# marbles_v70.net
KiCad netlist of a schematic drawn in EAGLE
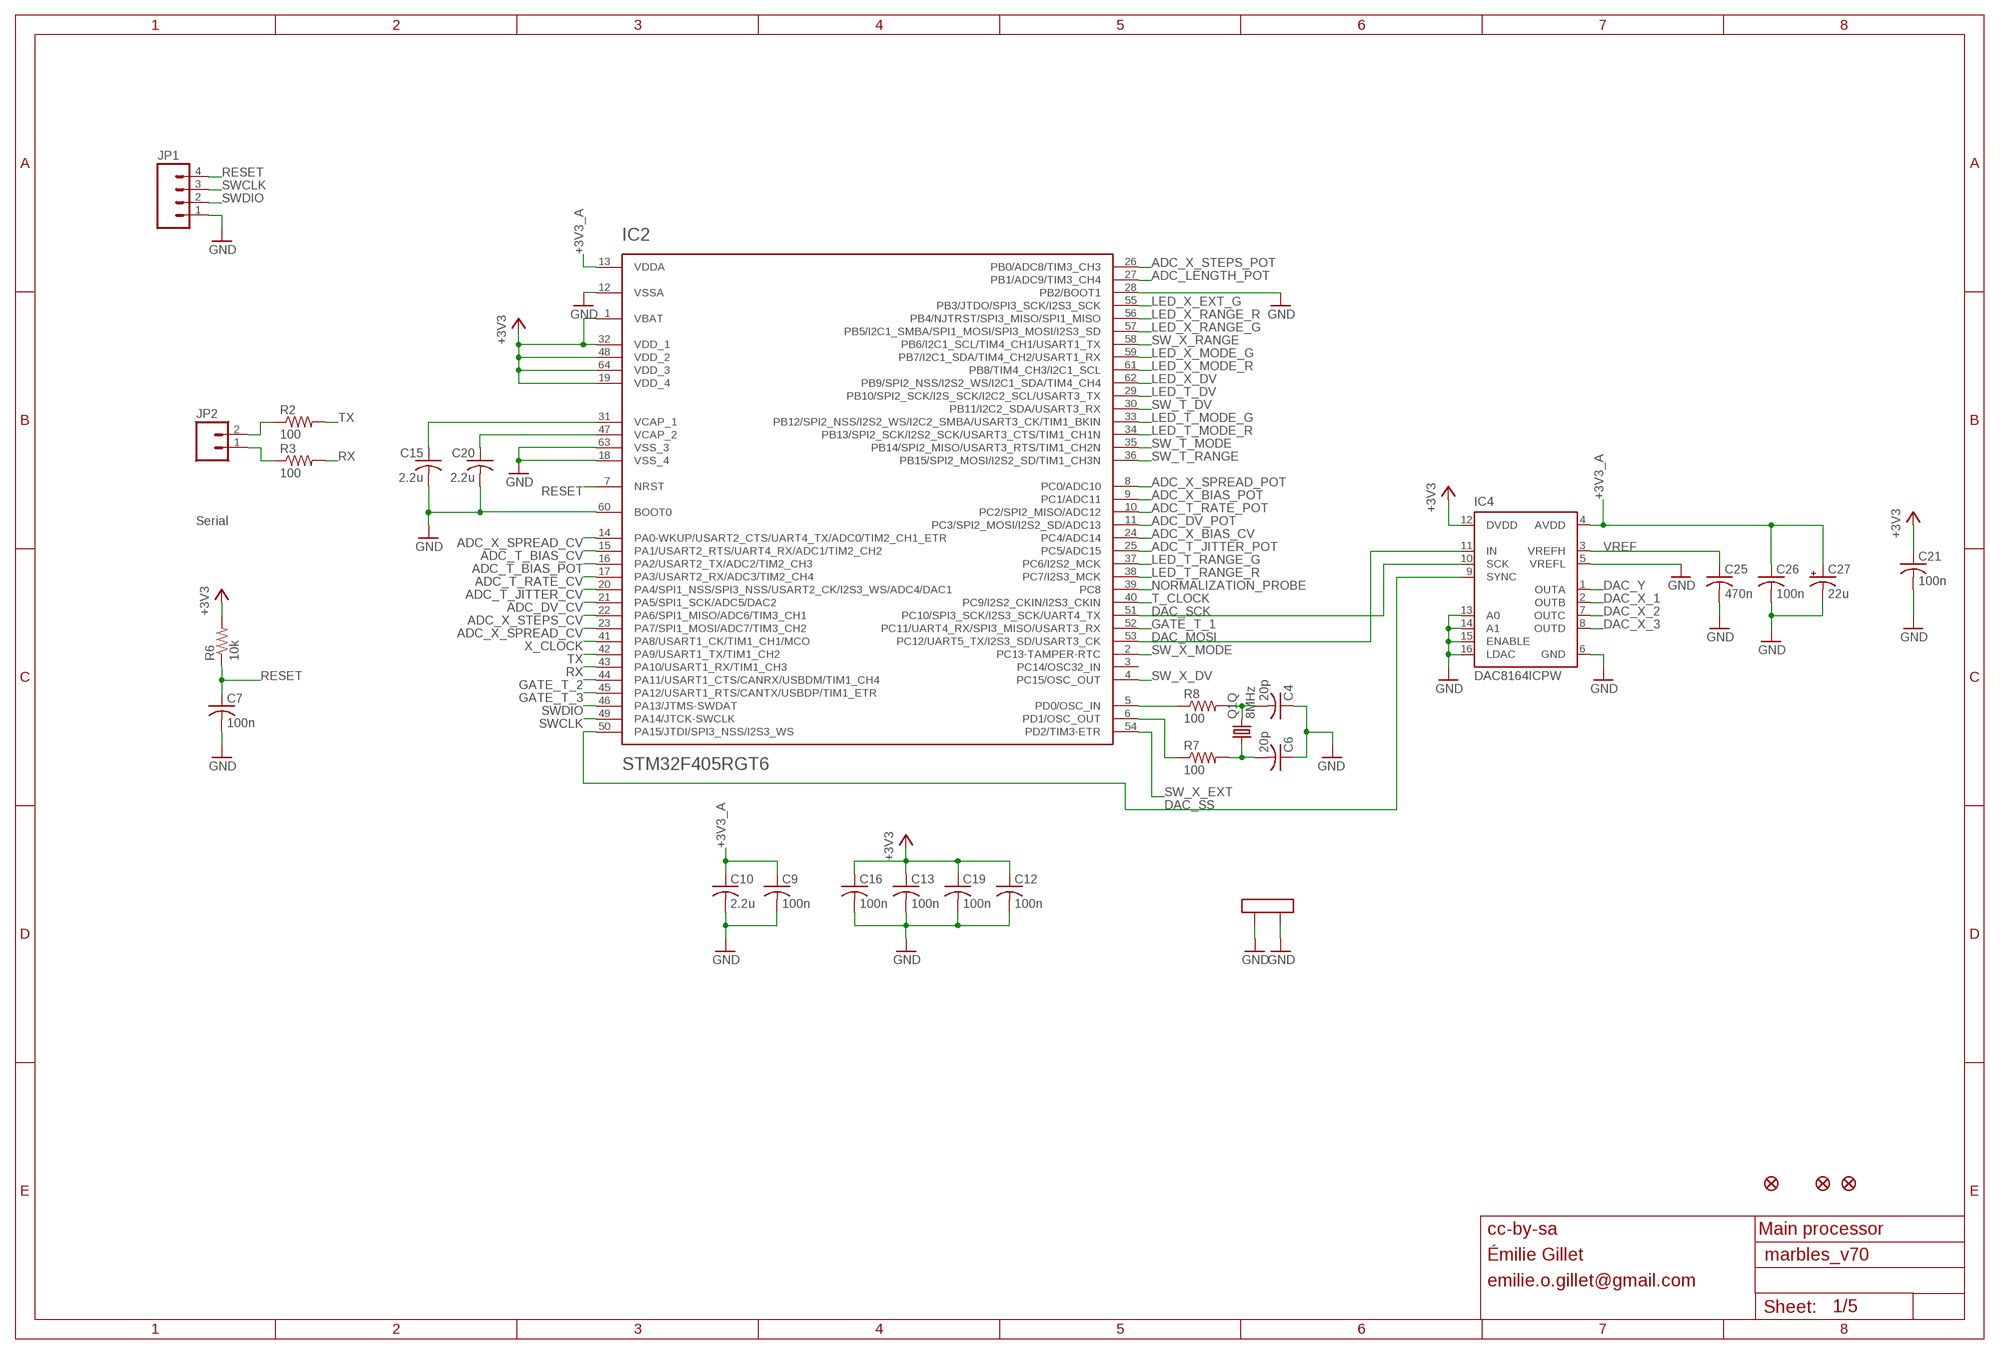
[diagram p0: schematic, sheet 1]
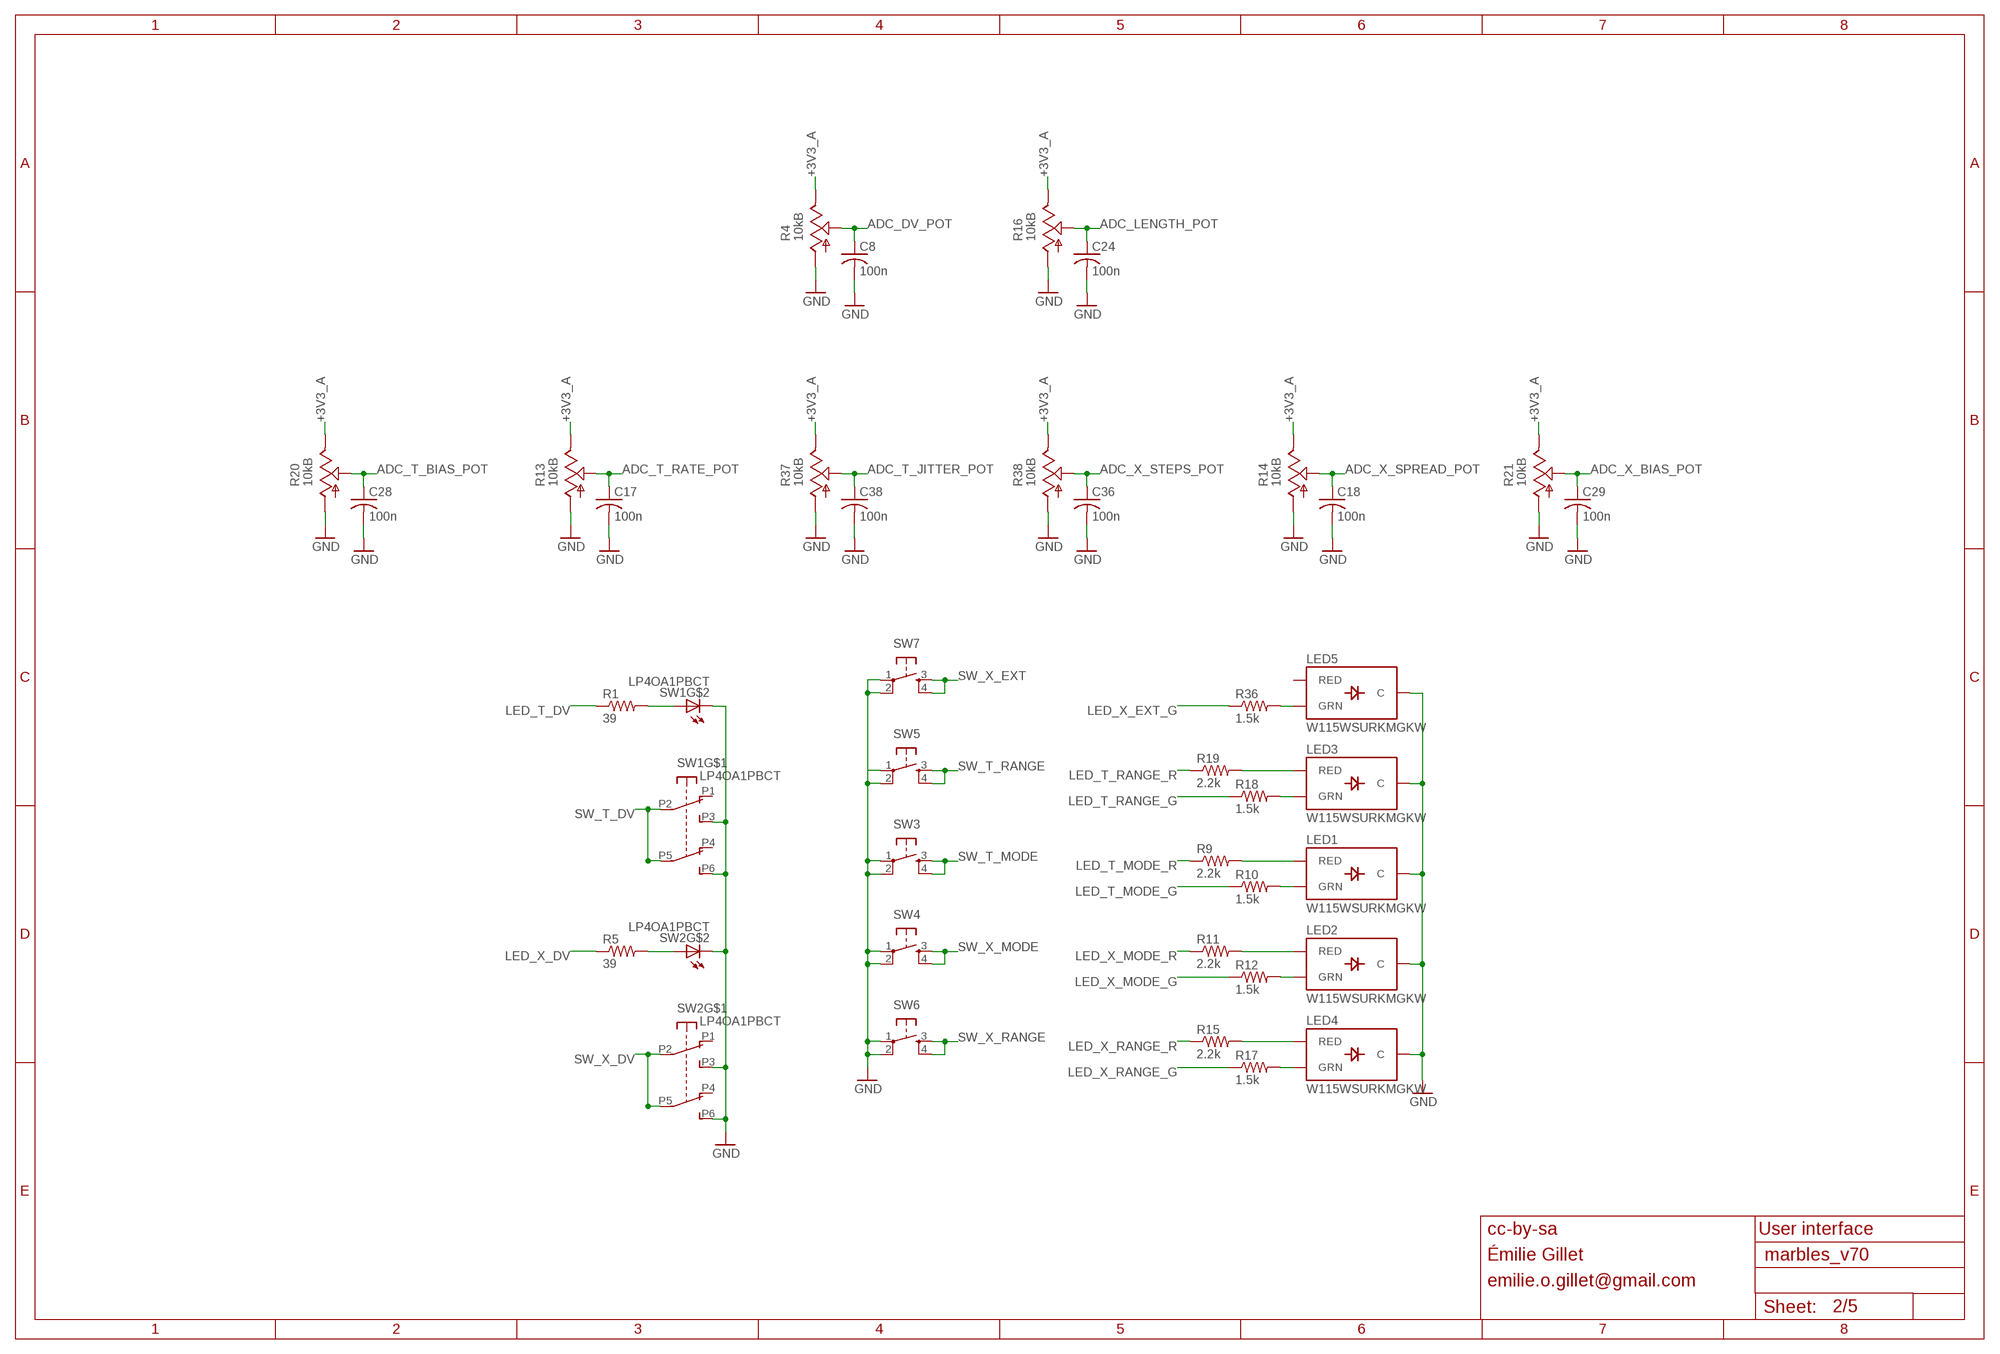
[diagram p1: schematic, sheet 2]
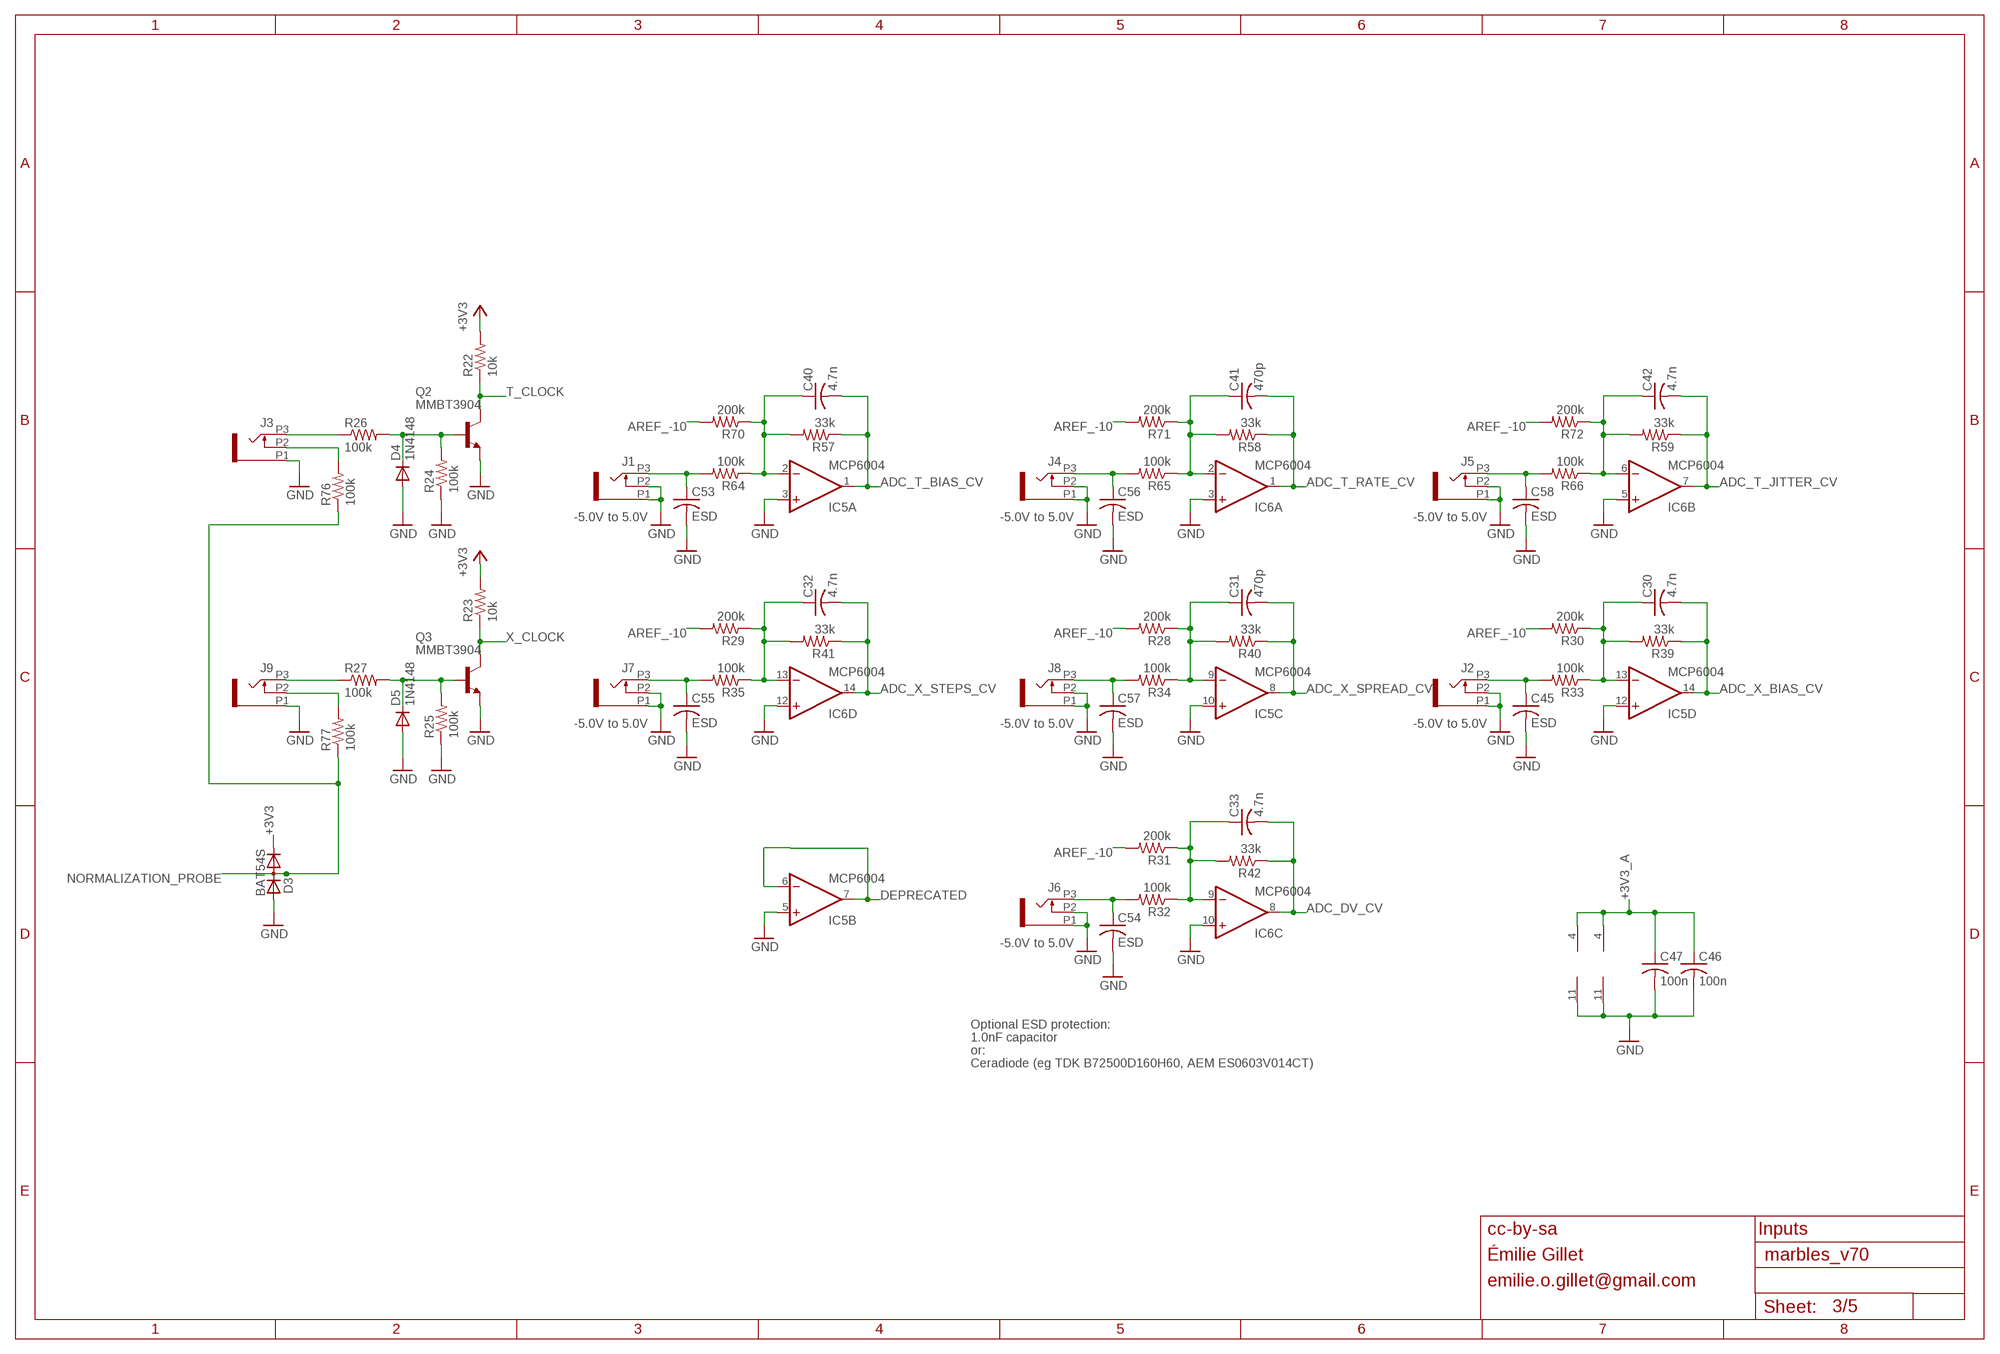
[diagram p2: schematic, sheet 3]
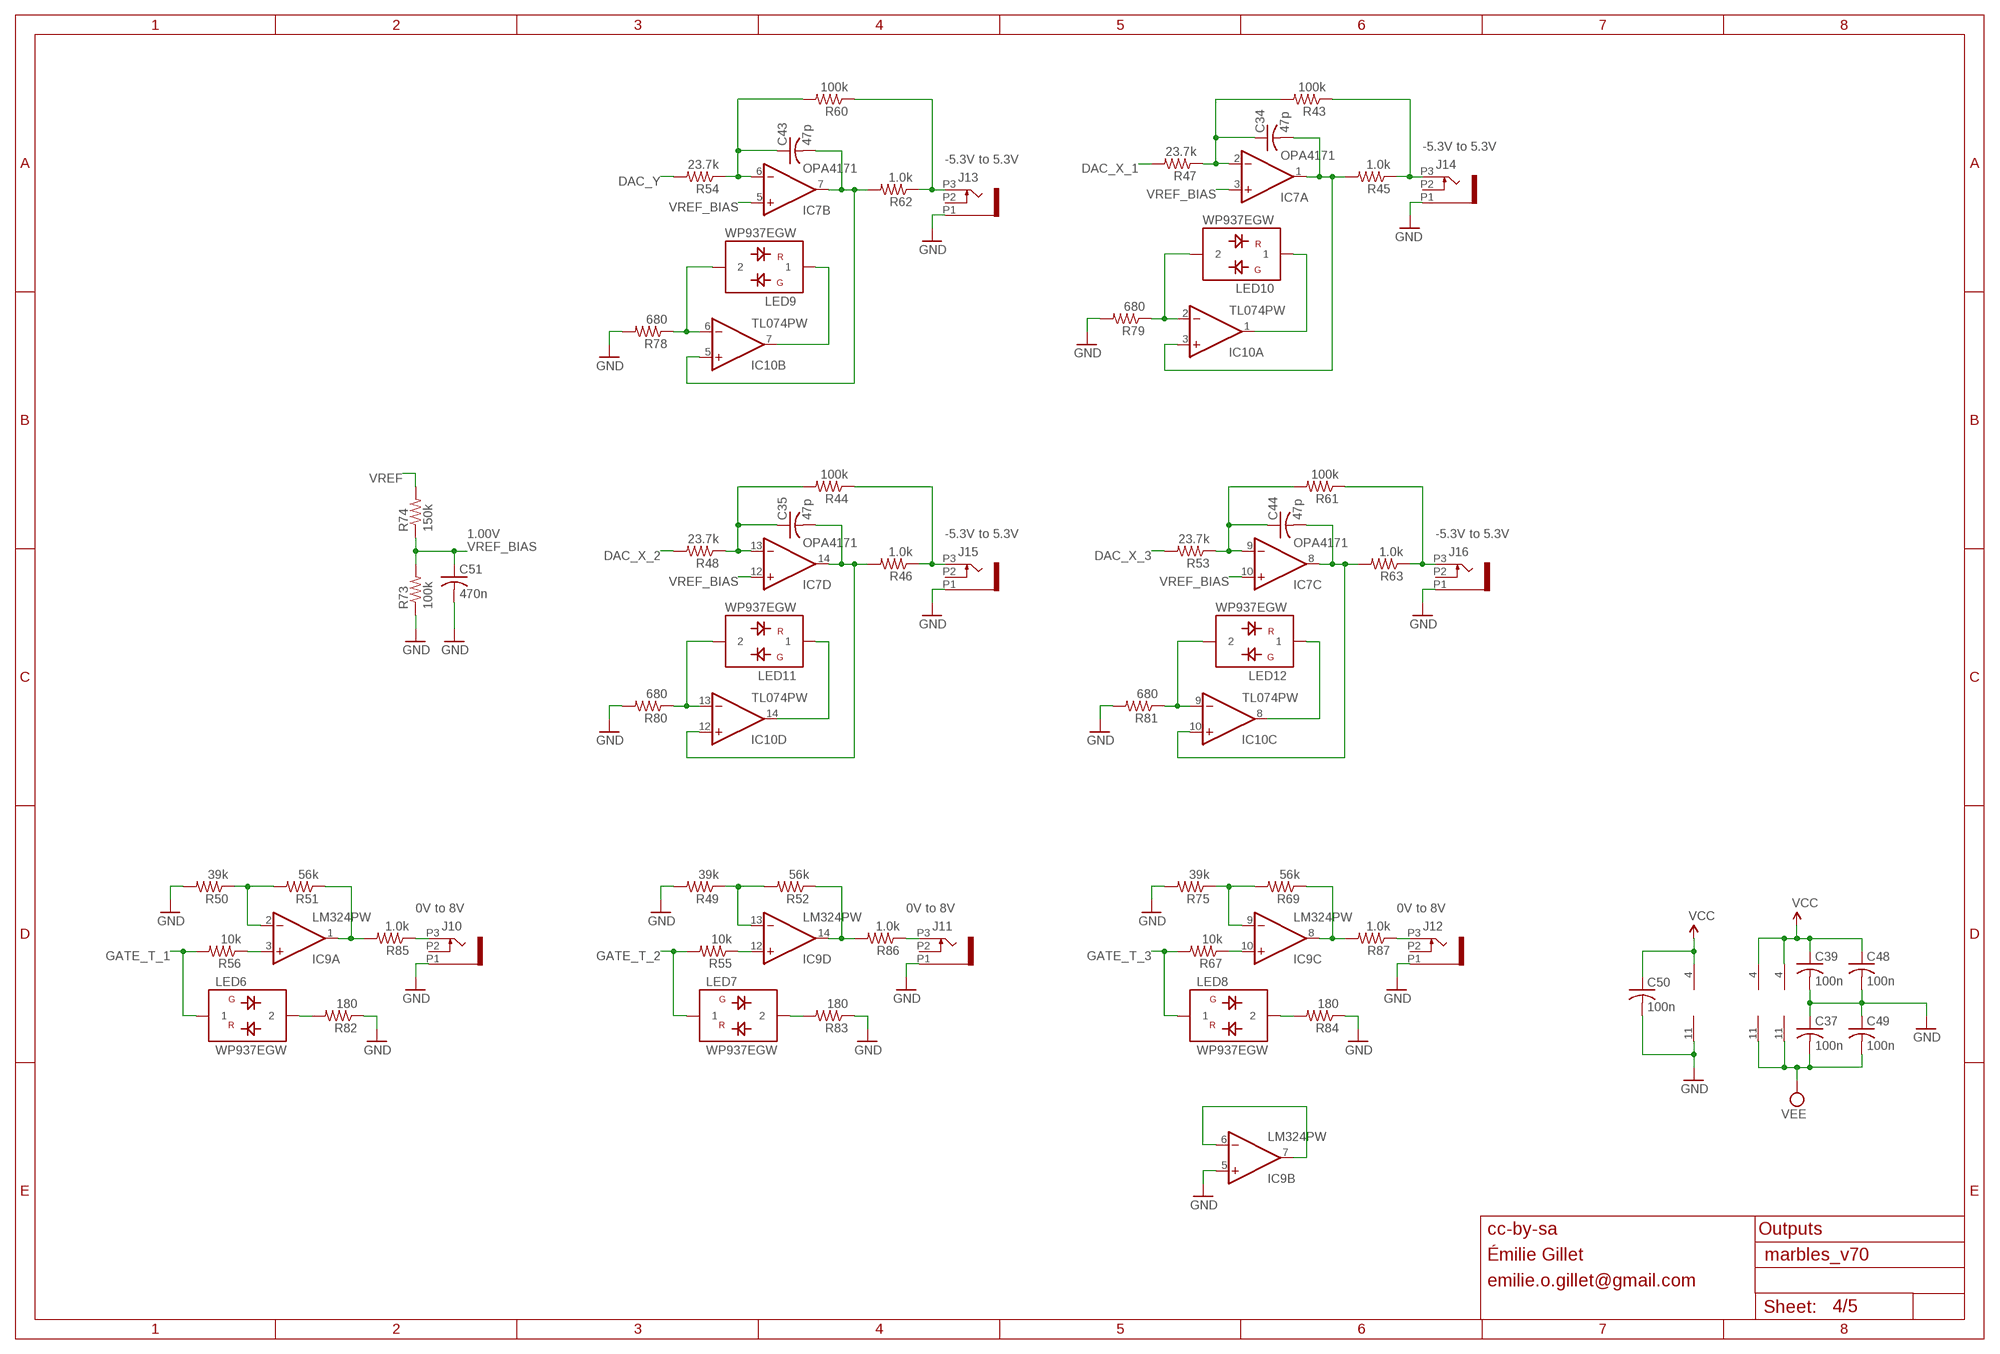
[diagram p3: schematic, sheet 4]
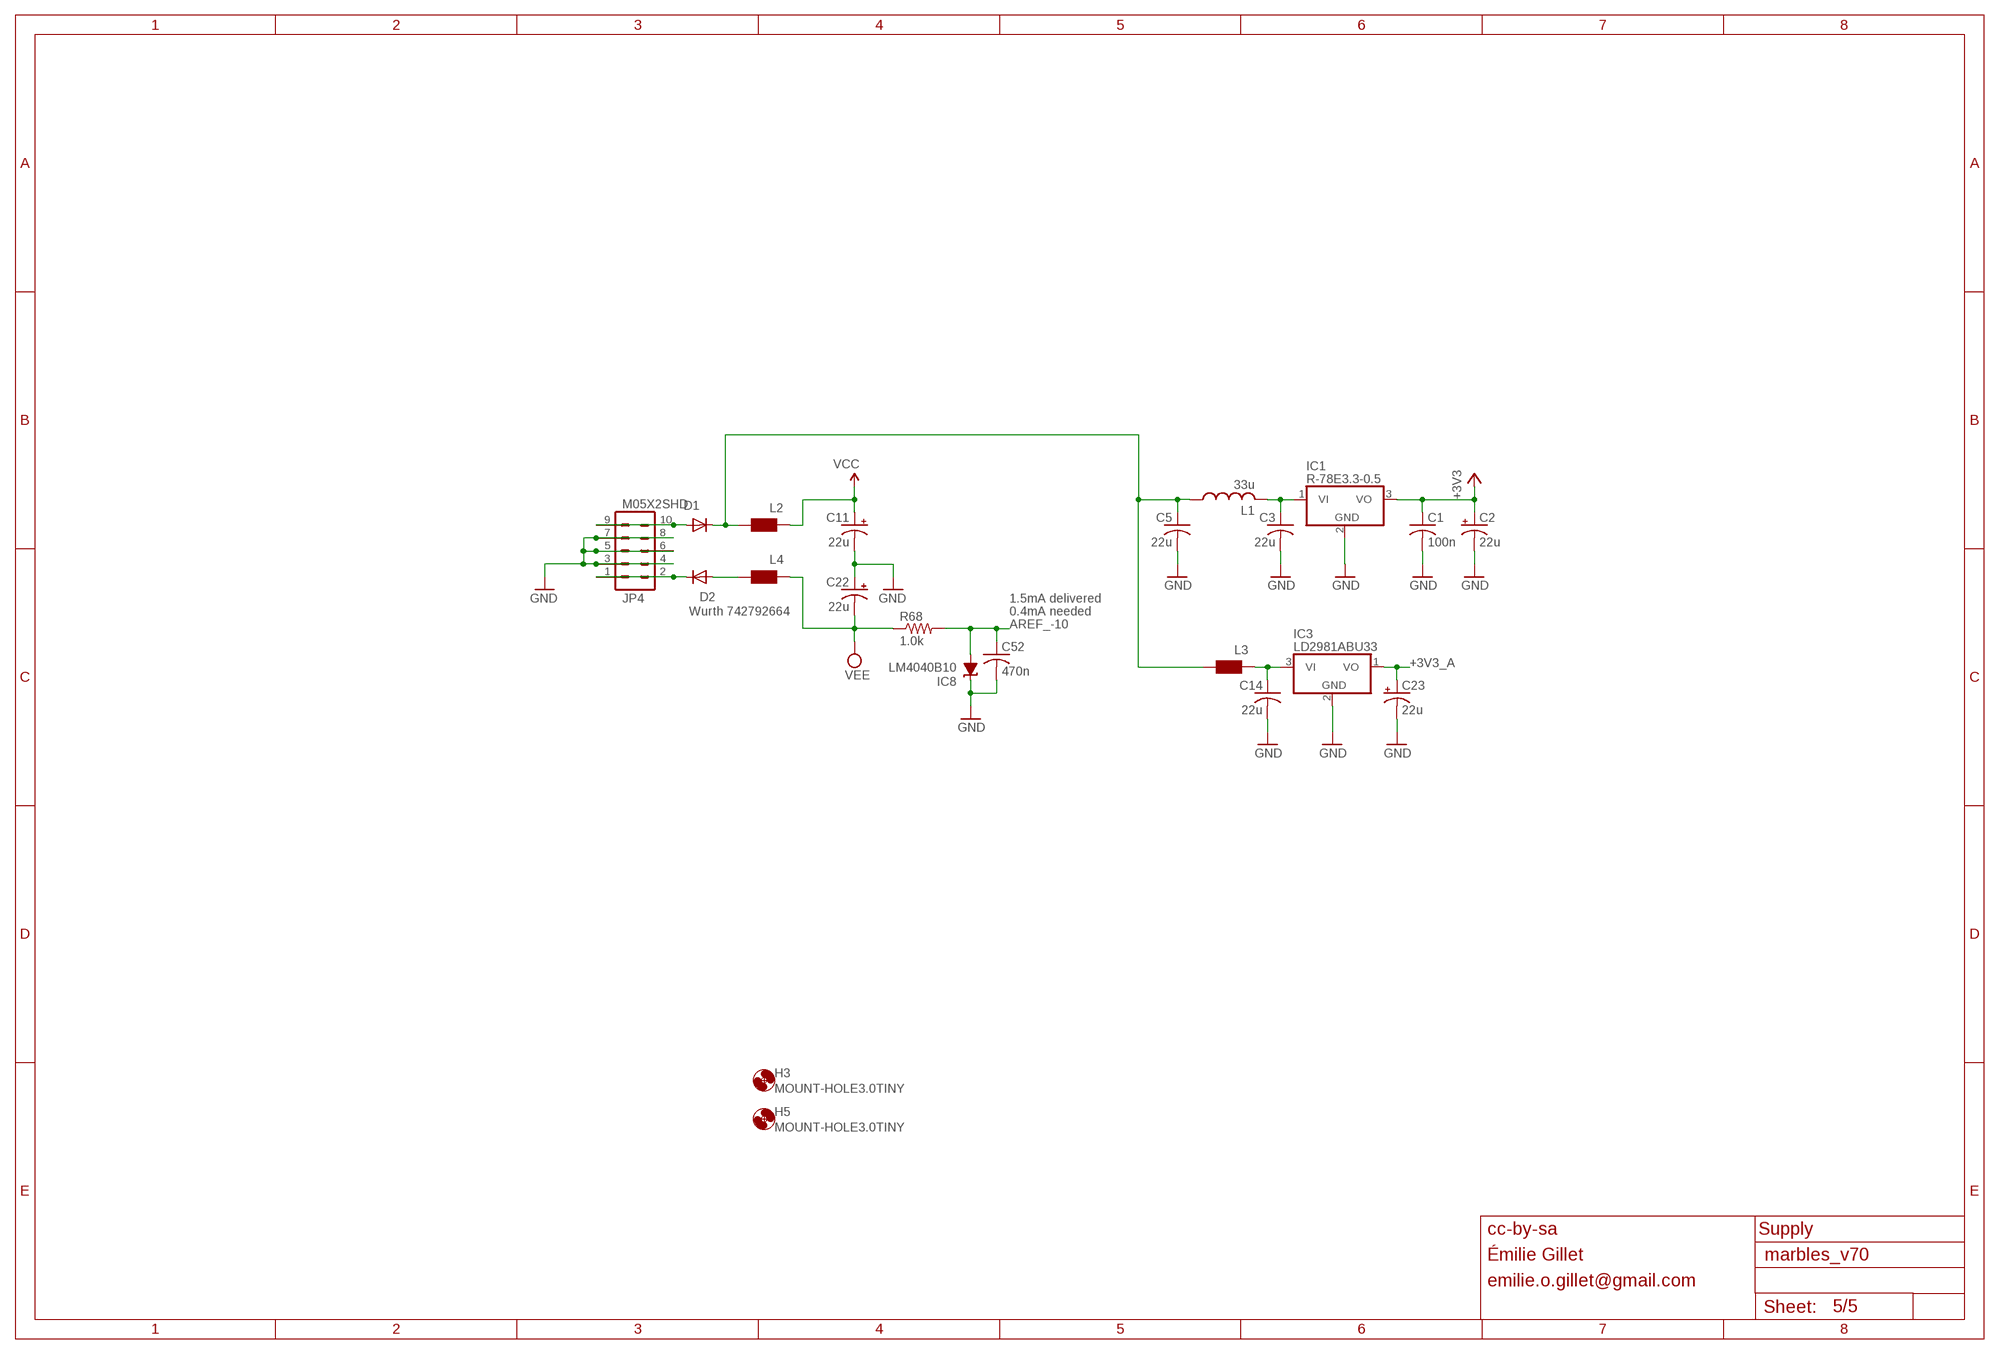
[diagram p4: schematic, sheet 5]

(export (version "E")
  (design (tool "Eeschema 10.0.6"))
  (components
    (comp (ref "C8")
      (value "100n")
      (footprint "eagle-import:C0402")
      (libsource (lib "eagle-import") (part "C-USC0402"))
    )
    (comp (ref "C17")
      (value "100n")
      (footprint "eagle-import:C0402")
      (libsource (lib "eagle-import") (part "C-USC0402"))
    )
    (comp (ref "C18")
      (value "100n")
      (footprint "eagle-import:C0402")
      (libsource (lib "eagle-import") (part "C-USC0402"))
    )
    (comp (ref "C24")
      (value "100n")
      (footprint "eagle-import:C0402")
      (libsource (lib "eagle-import") (part "C-USC0402"))
    )
    (comp (ref "C28")
      (value "100n")
      (footprint "eagle-import:C0402")
      (libsource (lib "eagle-import") (part "C-USC0402"))
    )
    (comp (ref "C29")
      (value "100n")
      (footprint "eagle-import:C0402")
      (libsource (lib "eagle-import") (part "C-USC0402"))
    )
    (comp (ref "C36")
      (value "100n")
      (footprint "eagle-import:C0402")
      (libsource (lib "eagle-import") (part "C-USC0402"))
    )
    (comp (ref "C38")
      (value "100n")
      (footprint "eagle-import:C0402")
      (libsource (lib "eagle-import") (part "C-USC0402"))
    )
    (comp (ref "LED1")
      (value "W115WSURKMGKW")
      (footprint "eagle-import:LED-BICOLOR-THROUGHHOLE-2.54")
      (libsource (lib "eagle-import") (part "LED-BICOLOR-THROUGHHOLE2.54"))
    )
    (comp (ref "LED2")
      (value "W115WSURKMGKW")
      (footprint "eagle-import:LED-BICOLOR-THROUGHHOLE-2.54")
      (libsource (lib "eagle-import") (part "LED-BICOLOR-THROUGHHOLE2.54"))
    )
    (comp (ref "LED3")
      (value "W115WSURKMGKW")
      (footprint "eagle-import:LED-BICOLOR-THROUGHHOLE-2.54")
      (libsource (lib "eagle-import") (part "LED-BICOLOR-THROUGHHOLE2.54"))
    )
    (comp (ref "LED4")
      (value "W115WSURKMGKW")
      (footprint "eagle-import:LED-BICOLOR-THROUGHHOLE-2.54")
      (libsource (lib "eagle-import") (part "LED-BICOLOR-THROUGHHOLE2.54"))
    )
    (comp (ref "LED5")
      (value "W115WSURKMGKW")
      (footprint "eagle-import:LED-BICOLOR-THROUGHHOLE-2.54")
      (libsource (lib "eagle-import") (part "LED-BICOLOR-THROUGHHOLE2.54"))
    )
    (comp (ref "R1")
      (value "39")
      (footprint "eagle-import:R0402")
      (libsource (lib "eagle-import") (part "R-US_R0402"))
    )
    (comp (ref "R4")
      (value "10kB")
      (footprint "eagle-import:ALPS_POT_VERTICAL_PS")
      (libsource (lib "eagle-import") (part "POT_USVERTICAL_PS"))
    )
    (comp (ref "R5")
      (value "39")
      (footprint "eagle-import:R0402")
      (libsource (lib "eagle-import") (part "R-US_R0402"))
    )
    (comp (ref "R9")
      (value "2.2k")
      (footprint "eagle-import:R0402")
      (libsource (lib "eagle-import") (part "R-US_R0402"))
    )
    (comp (ref "R10")
      (value "1.5k")
      (footprint "eagle-import:R0402")
      (libsource (lib "eagle-import") (part "R-US_R0402"))
    )
    (comp (ref "R11")
      (value "2.2k")
      (footprint "eagle-import:R0402")
      (libsource (lib "eagle-import") (part "R-US_R0402"))
    )
    (comp (ref "R12")
      (value "1.5k")
      (footprint "eagle-import:R0402")
      (libsource (lib "eagle-import") (part "R-US_R0402"))
    )
    (comp (ref "R13")
      (value "10kB")
      (footprint "eagle-import:ALPS_POT_VERTICAL_PS")
      (libsource (lib "eagle-import") (part "POT_USVERTICAL_PS"))
    )
    (comp (ref "R14")
      (value "10kB")
      (footprint "eagle-import:ALPS_POT_VERTICAL_PS")
      (libsource (lib "eagle-import") (part "POT_USVERTICAL_PS"))
    )
    (comp (ref "R15")
      (value "2.2k")
      (footprint "eagle-import:R0402")
      (libsource (lib "eagle-import") (part "R-US_R0402"))
    )
    (comp (ref "R16")
      (value "10kB")
      (footprint "eagle-import:ALPS_POT_VERTICAL_PS")
      (libsource (lib "eagle-import") (part "POT_USVERTICAL_PS"))
    )
    (comp (ref "R17")
      (value "1.5k")
      (footprint "eagle-import:R0402")
      (libsource (lib "eagle-import") (part "R-US_R0402"))
    )
    (comp (ref "R18")
      (value "1.5k")
      (footprint "eagle-import:R0402")
      (libsource (lib "eagle-import") (part "R-US_R0402"))
    )
    (comp (ref "R19")
      (value "2.2k")
      (footprint "eagle-import:R0402")
      (libsource (lib "eagle-import") (part "R-US_R0402"))
    )
    (comp (ref "R20")
      (value "10kB")
      (footprint "eagle-import:ALPS_POT_VERTICAL_PS")
      (libsource (lib "eagle-import") (part "POT_USVERTICAL_PS"))
    )
    (comp (ref "R21")
      (value "10kB")
      (footprint "eagle-import:ALPS_POT_VERTICAL_PS")
      (libsource (lib "eagle-import") (part "POT_USVERTICAL_PS"))
    )
    (comp (ref "R36")
      (value "1.5k")
      (footprint "eagle-import:R0402")
      (libsource (lib "eagle-import") (part "R-US_R0402"))
    )
    (comp (ref "R37")
      (value "10kB")
      (footprint "eagle-import:ALPS_POT_VERTICAL_PS")
      (libsource (lib "eagle-import") (part "POT_USVERTICAL_PS"))
    )
    (comp (ref "R38")
      (value "10kB")
      (footprint "eagle-import:ALPS_POT_VERTICAL_PS")
      (libsource (lib "eagle-import") (part "POT_USVERTICAL_PS"))
    )
    (comp (ref "SW1")
      (value "LP4OA1PBCT")
      (footprint "eagle-import:LP4OA1PBCT")
      (libsource (lib "eagle-import") (part "LP4OA1PBCT"))
    )
    (comp (ref "SW2")
      (value "LP4OA1PBCT")
      (footprint "eagle-import:LP4OA1PBCT")
      (libsource (lib "eagle-import") (part "LP4OA1PBCT"))
    )
    (comp (ref "SW3")
      (value "TAC_SWITCHPTH")
      (footprint "eagle-import:TACTILE-PTH")
      (libsource (lib "eagle-import") (part "TAC_SWITCHPTH"))
    )
    (comp (ref "SW4")
      (value "TAC_SWITCHPTH")
      (footprint "eagle-import:TACTILE-PTH")
      (libsource (lib "eagle-import") (part "TAC_SWITCHPTH"))
    )
    (comp (ref "SW5")
      (value "TAC_SWITCHPTH")
      (footprint "eagle-import:TACTILE-PTH")
      (libsource (lib "eagle-import") (part "TAC_SWITCHPTH"))
    )
    (comp (ref "SW6")
      (value "TAC_SWITCHPTH")
      (footprint "eagle-import:TACTILE-PTH")
      (libsource (lib "eagle-import") (part "TAC_SWITCHPTH"))
    )
    (comp (ref "SW7")
      (value "TAC_SWITCHPTH")
      (footprint "eagle-import:TACTILE-PTH")
      (libsource (lib "eagle-import") (part "TAC_SWITCHPTH"))
    )
    (comp (ref "C34")
      (value "47p")
      (footprint "eagle-import:C0402")
      (libsource (lib "eagle-import") (part "C-USC0402"))
    )
    (comp (ref "C35")
      (value "47p")
      (footprint "eagle-import:C0402")
      (libsource (lib "eagle-import") (part "C-USC0402"))
    )
    (comp (ref "C37")
      (value "100n")
      (footprint "eagle-import:C0402")
      (libsource (lib "eagle-import") (part "C-USC0402"))
    )
    (comp (ref "C39")
      (value "100n")
      (footprint "eagle-import:C0402")
      (libsource (lib "eagle-import") (part "C-USC0402"))
    )
    (comp (ref "C43")
      (value "47p")
      (footprint "eagle-import:C0402")
      (libsource (lib "eagle-import") (part "C-USC0402"))
    )
    (comp (ref "C44")
      (value "47p")
      (footprint "eagle-import:C0402")
      (libsource (lib "eagle-import") (part "C-USC0402"))
    )
    (comp (ref "C48")
      (value "100n")
      (footprint "eagle-import:C0402")
      (libsource (lib "eagle-import") (part "C-USC0402"))
    )
    (comp (ref "C49")
      (value "100n")
      (footprint "eagle-import:C0402")
      (libsource (lib "eagle-import") (part "C-USC0402"))
    )
    (comp (ref "C50")
      (value "100n")
      (footprint "eagle-import:C0402")
      (libsource (lib "eagle-import") (part "C-USC0402"))
    )
    (comp (ref "C51")
      (value "470n")
      (footprint "eagle-import:C0402")
      (libsource (lib "eagle-import") (part "C-USC0402"))
    )
    (comp (ref "IC7")
      (value "OPA4171")
      (footprint "eagle-import:TSSOP14_065")
      (libsource (lib "eagle-import") (part "TL074PW"))
    )
    (comp (ref "IC9")
      (value "LM324PW")
      (footprint "eagle-import:TSSOP14_065")
      (libsource (lib "eagle-import") (part "TL074PW"))
    )
    (comp (ref "IC10")
      (value "TL074PW")
      (footprint "eagle-import:TSSOP14_065")
      (libsource (lib "eagle-import") (part "TL074PW"))
    )
    (comp (ref "J10")
      (value "PJ301_THONKICONN6")
      (footprint "eagle-import:WQP_PJ_301M6")
      (libsource (lib "eagle-import") (part "PJ301_THONKICONN6"))
    )
    (comp (ref "J11")
      (value "PJ301_THONKICONN6")
      (footprint "eagle-import:WQP_PJ_301M6")
      (libsource (lib "eagle-import") (part "PJ301_THONKICONN6"))
    )
    (comp (ref "J12")
      (value "PJ301_THONKICONN6")
      (footprint "eagle-import:WQP_PJ_301M6")
      (libsource (lib "eagle-import") (part "PJ301_THONKICONN6"))
    )
    (comp (ref "J13")
      (value "PJ301_THONKICONN6")
      (footprint "eagle-import:WQP_PJ_301M6")
      (libsource (lib "eagle-import") (part "PJ301_THONKICONN6"))
    )
    (comp (ref "J14")
      (value "PJ301_THONKICONN6")
      (footprint "eagle-import:WQP_PJ_301M6")
      (libsource (lib "eagle-import") (part "PJ301_THONKICONN6"))
    )
    (comp (ref "J15")
      (value "PJ301_THONKICONN6")
      (footprint "eagle-import:WQP_PJ_301M6")
      (libsource (lib "eagle-import") (part "PJ301_THONKICONN6"))
    )
    (comp (ref "J16")
      (value "PJ301_THONKICONN6")
      (footprint "eagle-import:WQP_PJ_301M6")
      (libsource (lib "eagle-import") (part "PJ301_THONKICONN6"))
    )
    (comp (ref "LED6")
      (value "WP937EGW")
      (footprint "eagle-import:LED3MM")
      (libsource (lib "eagle-import") (part "LED-BICOLOR-SHARED-THROUGHHOLE"))
    )
    (comp (ref "LED7")
      (value "WP937EGW")
      (footprint "eagle-import:LED3MM")
      (libsource (lib "eagle-import") (part "LED-BICOLOR-SHARED-THROUGHHOLE"))
    )
    (comp (ref "LED8")
      (value "WP937EGW")
      (footprint "eagle-import:LED3MM")
      (libsource (lib "eagle-import") (part "LED-BICOLOR-SHARED-THROUGHHOLE"))
    )
    (comp (ref "LED9")
      (value "WP937EGW")
      (footprint "eagle-import:LED3MM")
      (libsource (lib "eagle-import") (part "LED-BICOLOR-SHARED-THROUGHHOLE"))
    )
    (comp (ref "LED10")
      (value "WP937EGW")
      (footprint "eagle-import:LED3MM")
      (libsource (lib "eagle-import") (part "LED-BICOLOR-SHARED-THROUGHHOLE"))
    )
    (comp (ref "LED11")
      (value "WP937EGW")
      (footprint "eagle-import:LED3MM")
      (libsource (lib "eagle-import") (part "LED-BICOLOR-SHARED-THROUGHHOLE"))
    )
    (comp (ref "LED12")
      (value "WP937EGW")
      (footprint "eagle-import:LED3MM")
      (libsource (lib "eagle-import") (part "LED-BICOLOR-SHARED-THROUGHHOLE"))
    )
    (comp (ref "R43")
      (value "100k")
      (footprint "eagle-import:R0402")
      (libsource (lib "eagle-import") (part "R-US_R0402"))
    )
    (comp (ref "R44")
      (value "100k")
      (footprint "eagle-import:R0402")
      (libsource (lib "eagle-import") (part "R-US_R0402"))
    )
    (comp (ref "R45")
      (value "1.0k")
      (footprint "eagle-import:R0603")
      (libsource (lib "eagle-import") (part "R-US_R0603"))
    )
    (comp (ref "R46")
      (value "1.0k")
      (footprint "eagle-import:R0603")
      (libsource (lib "eagle-import") (part "R-US_R0603"))
    )
    (comp (ref "R47")
      (value "23.7k")
      (footprint "eagle-import:R0402")
      (libsource (lib "eagle-import") (part "R-US_R0402"))
    )
    (comp (ref "R48")
      (value "23.7k")
      (footprint "eagle-import:R0402")
      (libsource (lib "eagle-import") (part "R-US_R0402"))
    )
    (comp (ref "R49")
      (value "39k")
      (footprint "eagle-import:R0402")
      (libsource (lib "eagle-import") (part "R-US_R0402"))
    )
    (comp (ref "R50")
      (value "39k")
      (footprint "eagle-import:R0402")
      (libsource (lib "eagle-import") (part "R-US_R0402"))
    )
    (comp (ref "R51")
      (value "56k")
      (footprint "eagle-import:R0402")
      (libsource (lib "eagle-import") (part "R-US_R0402"))
    )
    (comp (ref "R52")
      (value "56k")
      (footprint "eagle-import:R0402")
      (libsource (lib "eagle-import") (part "R-US_R0402"))
    )
    (comp (ref "R53")
      (value "23.7k")
      (footprint "eagle-import:R0402")
      (libsource (lib "eagle-import") (part "R-US_R0402"))
    )
    (comp (ref "R54")
      (value "23.7k")
      (footprint "eagle-import:R0402")
      (libsource (lib "eagle-import") (part "R-US_R0402"))
    )
    (comp (ref "R55")
      (value "10k")
      (footprint "eagle-import:R0402")
      (libsource (lib "eagle-import") (part "R-US_R0402"))
    )
    (comp (ref "R56")
      (value "10k")
      (footprint "eagle-import:R0402")
      (libsource (lib "eagle-import") (part "R-US_R0402"))
    )
    (comp (ref "R60")
      (value "100k")
      (footprint "eagle-import:R0402")
      (libsource (lib "eagle-import") (part "R-US_R0402"))
    )
    (comp (ref "R61")
      (value "100k")
      (footprint "eagle-import:R0402")
      (libsource (lib "eagle-import") (part "R-US_R0402"))
    )
    (comp (ref "R62")
      (value "1.0k")
      (footprint "eagle-import:R0603")
      (libsource (lib "eagle-import") (part "R-US_R0603"))
    )
    (comp (ref "R63")
      (value "1.0k")
      (footprint "eagle-import:R0603")
      (libsource (lib "eagle-import") (part "R-US_R0603"))
    )
    (comp (ref "R67")
      (value "10k")
      (footprint "eagle-import:R0402")
      (libsource (lib "eagle-import") (part "R-US_R0402"))
    )
    (comp (ref "R69")
      (value "56k")
      (footprint "eagle-import:R0402")
      (libsource (lib "eagle-import") (part "R-US_R0402"))
    )
    (comp (ref "R73")
      (value "100k")
      (footprint "eagle-import:R0402")
      (libsource (lib "eagle-import") (part "R-US_R0402"))
    )
    (comp (ref "R74")
      (value "150k")
      (footprint "eagle-import:R0402")
      (libsource (lib "eagle-import") (part "R-US_R0402"))
    )
    (comp (ref "R75")
      (value "39k")
      (footprint "eagle-import:R0402")
      (libsource (lib "eagle-import") (part "R-US_R0402"))
    )
    (comp (ref "R78")
      (value "680")
      (footprint "eagle-import:R0402")
      (libsource (lib "eagle-import") (part "R-US_R0402"))
    )
    (comp (ref "R79")
      (value "680")
      (footprint "eagle-import:R0402")
      (libsource (lib "eagle-import") (part "R-US_R0402"))
    )
    (comp (ref "R80")
      (value "680")
      (footprint "eagle-import:R0402")
      (libsource (lib "eagle-import") (part "R-US_R0402"))
    )
    (comp (ref "R81")
      (value "680")
      (footprint "eagle-import:R0402")
      (libsource (lib "eagle-import") (part "R-US_R0402"))
    )
    (comp (ref "R82")
      (value "180")
      (footprint "eagle-import:R0402")
      (libsource (lib "eagle-import") (part "R-US_R0402"))
    )
    (comp (ref "R83")
      (value "180")
      (footprint "eagle-import:R0402")
      (libsource (lib "eagle-import") (part "R-US_R0402"))
    )
    (comp (ref "R84")
      (value "180")
      (footprint "eagle-import:R0402")
      (libsource (lib "eagle-import") (part "R-US_R0402"))
    )
    (comp (ref "R85")
      (value "1.0k")
      (footprint "eagle-import:R0603")
      (libsource (lib "eagle-import") (part "R-US_R0603"))
    )
    (comp (ref "R86")
      (value "1.0k")
      (footprint "eagle-import:R0603")
      (libsource (lib "eagle-import") (part "R-US_R0603"))
    )
    (comp (ref "R87")
      (value "1.0k")
      (footprint "eagle-import:R0603")
      (libsource (lib "eagle-import") (part "R-US_R0603"))
    )
    (comp (ref "C4")
      (value "20p")
      (footprint "eagle-import:C0402")
      (libsource (lib "eagle-import") (part "C-USC0402"))
    )
    (comp (ref "C6")
      (value "20p")
      (footprint "eagle-import:C0402")
      (libsource (lib "eagle-import") (part "C-USC0402"))
    )
    (comp (ref "C7")
      (value "100n")
      (footprint "eagle-import:C0402")
      (libsource (lib "eagle-import") (part "C-USC0402"))
    )
    (comp (ref "C9")
      (value "100n")
      (footprint "eagle-import:C0402")
      (libsource (lib "eagle-import") (part "C-USC0402"))
    )
    (comp (ref "C10")
      (value "2.2u")
      (footprint "eagle-import:C0805")
      (libsource (lib "eagle-import") (part "C-USC0805"))
    )
    (comp (ref "C12")
      (value "100n")
      (footprint "eagle-import:C0402")
      (libsource (lib "eagle-import") (part "C-USC0402"))
    )
    (comp (ref "C13")
      (value "100n")
      (footprint "eagle-import:C0402")
      (libsource (lib "eagle-import") (part "C-USC0402"))
    )
    (comp (ref "C15")
      (value "2.2u")
      (footprint "eagle-import:C0805")
      (libsource (lib "eagle-import") (part "C-USC0805"))
    )
    (comp (ref "C16")
      (value "100n")
      (footprint "eagle-import:C0402")
      (libsource (lib "eagle-import") (part "C-USC0402"))
    )
    (comp (ref "C19")
      (value "100n")
      (footprint "eagle-import:C0402")
      (libsource (lib "eagle-import") (part "C-USC0402"))
    )
    (comp (ref "C20")
      (value "2.2u")
      (footprint "eagle-import:C0805")
      (libsource (lib "eagle-import") (part "C-USC0805"))
    )
    (comp (ref "C21")
      (value "100n")
      (footprint "eagle-import:C0402")
      (libsource (lib "eagle-import") (part "C-USC0402"))
    )
    (comp (ref "C25")
      (value "470n")
      (footprint "eagle-import:C0402")
      (libsource (lib "eagle-import") (part "C-USC0402"))
    )
    (comp (ref "C26")
      (value "100n")
      (footprint "eagle-import:C0402")
      (libsource (lib "eagle-import") (part "C-USC0402"))
    )
    (comp (ref "C27")
      (value "22u")
      (footprint "eagle-import:PANASONIC_C")
      (libsource (lib "eagle-import") (part "CPOL-USC"))
    )
    (comp (ref "F1")
      (value "FIDUCIAL1X2")
      (footprint "eagle-import:FIDUCIAL-1X2")
      (libsource (lib "eagle-import") (part "FIDUCIAL1X2"))
    )
    (comp (ref "F2")
      (value "FIDUCIAL1X2")
      (footprint "eagle-import:FIDUCIAL-1X2")
      (libsource (lib "eagle-import") (part "FIDUCIAL1X2"))
    )
    (comp (ref "F3")
      (value "FIDUCIAL1X2")
      (footprint "eagle-import:FIDUCIAL-1X2")
      (libsource (lib "eagle-import") (part "FIDUCIAL1X2"))
    )
    (comp (ref "IC2")
      (value "STM32F405RGT6")
      (footprint "eagle-import:TQFP-10X10-64")
      (libsource (lib "eagle-import") (part "STM32F20X"))
    )
    (comp (ref "IC4")
      (value "DAC8164ICPW")
      (footprint "eagle-import:SOP65P640X110-16N")
      (libsource (lib "eagle-import") (part "DAC8564"))
    )
    (comp (ref "JP1")
      (value "M04PTH")
      (footprint "eagle-import:1X04")
      (libsource (lib "eagle-import") (part "M04PTH"))
    )
    (comp (ref "JP2")
      (value "M02PTH")
      (footprint "eagle-import:1X02")
      (libsource (lib "eagle-import") (part "M02PTH"))
    )
    (comp (ref "Q1")
      (value "8MHz")
      (footprint "eagle-import:CTS406")
      (libsource (lib "eagle-import") (part "CRYSTAL"))
    )
    (comp (ref "R2")
      (value "100")
      (footprint "eagle-import:R0402")
      (libsource (lib "eagle-import") (part "R-US_R0402"))
    )
    (comp (ref "R3")
      (value "100")
      (footprint "eagle-import:R0402")
      (libsource (lib "eagle-import") (part "R-US_R0402"))
    )
    (comp (ref "R6")
      (value "10k")
      (footprint "eagle-import:R0402")
      (libsource (lib "eagle-import") (part "R-US_R0402"))
    )
    (comp (ref "R7")
      (value "100")
      (footprint "eagle-import:R0402")
      (libsource (lib "eagle-import") (part "R-US_R0402"))
    )
    (comp (ref "R8")
      (value "100")
      (footprint "eagle-import:R0402")
      (libsource (lib "eagle-import") (part "R-US_R0402"))
    )
    (comp (ref "C1")
      (value "100n")
      (footprint "eagle-import:C0402")
      (libsource (lib "eagle-import") (part "C-USC0402"))
    )
    (comp (ref "C2")
      (value "22u")
      (footprint "eagle-import:PANASONIC_C")
      (libsource (lib "eagle-import") (part "CPOL-USC"))
    )
    (comp (ref "C3")
      (value "22u")
      (footprint "eagle-import:C1206")
      (libsource (lib "eagle-import") (part "C-USC1206"))
    )
    (comp (ref "C5")
      (value "22u")
      (footprint "eagle-import:C1206")
      (libsource (lib "eagle-import") (part "C-USC1206"))
    )
    (comp (ref "C11")
      (value "22u")
      (footprint "eagle-import:PANASONIC_C")
      (libsource (lib "eagle-import") (part "CPOL-USC"))
    )
    (comp (ref "C14")
      (value "22u")
      (footprint "eagle-import:C1206")
      (libsource (lib "eagle-import") (part "C-USC1206"))
    )
    (comp (ref "C22")
      (value "22u")
      (footprint "eagle-import:PANASONIC_C")
      (libsource (lib "eagle-import") (part "CPOL-USC"))
    )
    (comp (ref "C23")
      (value "22u")
      (footprint "eagle-import:PANASONIC_C")
      (libsource (lib "eagle-import") (part "CPOL-USC"))
    )
    (comp (ref "C52")
      (value "470n")
      (footprint "eagle-import:C0402")
      (libsource (lib "eagle-import") (part "C-USC0402"))
    )
    (comp (ref "D1")
      (value "1N5819HW")
      (footprint "eagle-import:SOD123")
      (libsource (lib "eagle-import") (part "DIODE-SOD123"))
    )
    (comp (ref "D2")
      (value "1N5819HW")
      (footprint "eagle-import:SOD123")
      (libsource (lib "eagle-import") (part "DIODE-SOD123"))
    )
    (comp (ref "H3")
      (value "MOUNT-HOLE3.0TINY")
      (footprint "eagle-import:3,0TINY")
      (libsource (lib "eagle-import") (part "MOUNT-HOLE3.0TINY"))
    )
    (comp (ref "H5")
      (value "MOUNT-HOLE3.0TINY")
      (footprint "eagle-import:3,0TINY")
      (libsource (lib "eagle-import") (part "MOUNT-HOLE3.0TINY"))
    )
    (comp (ref "IC1")
      (value "R-78E3.3-0.5")
      (footprint "eagle-import:WE78")
      (libsource (lib "eagle-import") (part "WE173950378"))
    )
    (comp (ref "IC3")
      (value "LD2981ABU33")
      (footprint "eagle-import:SOT89")
      (libsource (lib "eagle-import") (part "LD2981ABU"))
    )
    (comp (ref "IC8")
      (value "LM4040B10")
      (footprint "eagle-import:DBZ_R-PDSO-G3")
      (libsource (lib "eagle-import") (part "LM4041DBZB12"))
    )
    (comp (ref "JP4")
      (value "M05X2SHD")
      (footprint "eagle-import:2X5-SHROUDED")
      (libsource (lib "eagle-import") (part "M05X2SHD"))
    )
    (comp (ref "L1")
      (value "33u")
      (footprint "eagle-import:L2012C")
      (libsource (lib "eagle-import") (part "L-USL2012C"))
    )
    (comp (ref "L2")
      (value "WE-CBF_0603")
      (footprint "eagle-import:0603")
      (libsource (lib "eagle-import") (part "WE-CBF_0603"))
    )
    (comp (ref "L3")
      (value "WE-CBF_0603")
      (footprint "eagle-import:0603")
      (libsource (lib "eagle-import") (part "WE-CBF_0603"))
    )
    (comp (ref "L4")
      (value "WE-CBF_0603")
      (footprint "eagle-import:0603")
      (libsource (lib "eagle-import") (part "WE-CBF_0603"))
    )
    (comp (ref "R68")
      (value "1.0k")
      (footprint "eagle-import:R0402")
      (libsource (lib "eagle-import") (part "R-US_R0402"))
    )
    (comp (ref "C30")
      (value "4.7n")
      (footprint "eagle-import:C0402")
      (libsource (lib "eagle-import") (part "C-USC0402"))
    )
    (comp (ref "C31")
      (value "470p")
      (footprint "eagle-import:C0402")
      (libsource (lib "eagle-import") (part "C-USC0402"))
    )
    (comp (ref "C32")
      (value "4.7n")
      (footprint "eagle-import:C0402")
      (libsource (lib "eagle-import") (part "C-USC0402"))
    )
    (comp (ref "C33")
      (value "4.7n")
      (footprint "eagle-import:C0402")
      (libsource (lib "eagle-import") (part "C-USC0402"))
    )
    (comp (ref "C40")
      (value "4.7n")
      (footprint "eagle-import:C0402")
      (libsource (lib "eagle-import") (part "C-USC0402"))
    )
    (comp (ref "C41")
      (value "470p")
      (footprint "eagle-import:C0402")
      (libsource (lib "eagle-import") (part "C-USC0402"))
    )
    (comp (ref "C42")
      (value "4.7n")
      (footprint "eagle-import:C0402")
      (libsource (lib "eagle-import") (part "C-USC0402"))
    )
    (comp (ref "C45")
      (value "ESD")
      (footprint "eagle-import:C0603")
      (libsource (lib "eagle-import") (part "C-USC0603"))
    )
    (comp (ref "C46")
      (value "100n")
      (footprint "eagle-import:C0402")
      (libsource (lib "eagle-import") (part "C-USC0402"))
    )
    (comp (ref "C47")
      (value "100n")
      (footprint "eagle-import:C0402")
      (libsource (lib "eagle-import") (part "C-USC0402"))
    )
    (comp (ref "C53")
      (value "ESD")
      (footprint "eagle-import:C0603")
      (libsource (lib "eagle-import") (part "C-USC0603"))
    )
    (comp (ref "C54")
      (value "ESD")
      (footprint "eagle-import:C0603")
      (libsource (lib "eagle-import") (part "C-USC0603"))
    )
    (comp (ref "C55")
      (value "ESD")
      (footprint "eagle-import:C0603")
      (libsource (lib "eagle-import") (part "C-USC0603"))
    )
    (comp (ref "C56")
      (value "ESD")
      (footprint "eagle-import:C0603")
      (libsource (lib "eagle-import") (part "C-USC0603"))
    )
    (comp (ref "C57")
      (value "ESD")
      (footprint "eagle-import:C0603")
      (libsource (lib "eagle-import") (part "C-USC0603"))
    )
    (comp (ref "C58")
      (value "ESD")
      (footprint "eagle-import:C0603")
      (libsource (lib "eagle-import") (part "C-USC0603"))
    )
    (comp (ref "D3")
      (value "BAT54S")
      (footprint "eagle-import:SOT23")
      (libsource (lib "eagle-import") (part "DIODE_2CACA-SOT23"))
    )
    (comp (ref "D4")
      (value "1N4148")
      (footprint "eagle-import:SOD523")
      (libsource (lib "eagle-import") (part "DIODE-SOD523"))
    )
    (comp (ref "D5")
      (value "1N4148")
      (footprint "eagle-import:SOD523")
      (libsource (lib "eagle-import") (part "DIODE-SOD523"))
    )
    (comp (ref "IC5")
      (value "MCP6004")
      (footprint "eagle-import:TSSOP14_065")
      (libsource (lib "eagle-import") (part "TL074PW"))
    )
    (comp (ref "IC6")
      (value "MCP6004")
      (footprint "eagle-import:TSSOP14_065")
      (libsource (lib "eagle-import") (part "TL074PW"))
    )
    (comp (ref "J1")
      (value "PJ301_THONKICONN6")
      (footprint "eagle-import:WQP_PJ_301M6")
      (libsource (lib "eagle-import") (part "PJ301_THONKICONN6"))
    )
    (comp (ref "J2")
      (value "PJ301_THONKICONN6")
      (footprint "eagle-import:WQP_PJ_301M6")
      (libsource (lib "eagle-import") (part "PJ301_THONKICONN6"))
    )
    (comp (ref "J3")
      (value "PJ301_THONKICONN6")
      (footprint "eagle-import:WQP_PJ_301M6")
      (libsource (lib "eagle-import") (part "PJ301_THONKICONN6"))
    )
    (comp (ref "J4")
      (value "PJ301_THONKICONN6")
      (footprint "eagle-import:WQP_PJ_301M6")
      (libsource (lib "eagle-import") (part "PJ301_THONKICONN6"))
    )
    (comp (ref "J5")
      (value "PJ301_THONKICONN6")
      (footprint "eagle-import:WQP_PJ_301M6")
      (libsource (lib "eagle-import") (part "PJ301_THONKICONN6"))
    )
    (comp (ref "J6")
      (value "PJ301_THONKICONN6")
      (footprint "eagle-import:WQP_PJ_301M6")
      (libsource (lib "eagle-import") (part "PJ301_THONKICONN6"))
    )
    (comp (ref "J7")
      (value "PJ301_THONKICONN6")
      (footprint "eagle-import:WQP_PJ_301M6")
      (libsource (lib "eagle-import") (part "PJ301_THONKICONN6"))
    )
    (comp (ref "J8")
      (value "PJ301_THONKICONN6")
      (footprint "eagle-import:WQP_PJ_301M6")
      (libsource (lib "eagle-import") (part "PJ301_THONKICONN6"))
    )
    (comp (ref "J9")
      (value "PJ301_THONKICONN6")
      (footprint "eagle-import:WQP_PJ_301M6")
      (libsource (lib "eagle-import") (part "PJ301_THONKICONN6"))
    )
    (comp (ref "Q2")
      (value "MMBT3904")
      (footprint "eagle-import:SOT23-BEC")
      (libsource (lib "eagle-import") (part "-NPN-SOT23-BECMMBT3904LT1"))
    )
    (comp (ref "Q3")
      (value "MMBT3904")
      (footprint "eagle-import:SOT23-BEC")
      (libsource (lib "eagle-import") (part "-NPN-SOT23-BECMMBT3904LT1"))
    )
    (comp (ref "R22")
      (value "10k")
      (footprint "eagle-import:R0402")
      (libsource (lib "eagle-import") (part "R-US_R0402"))
    )
    (comp (ref "R23")
      (value "10k")
      (footprint "eagle-import:R0402")
      (libsource (lib "eagle-import") (part "R-US_R0402"))
    )
    (comp (ref "R24")
      (value "100k")
      (footprint "eagle-import:R0402")
      (libsource (lib "eagle-import") (part "R-US_R0402"))
    )
    (comp (ref "R25")
      (value "100k")
      (footprint "eagle-import:R0402")
      (libsource (lib "eagle-import") (part "R-US_R0402"))
    )
    (comp (ref "R26")
      (value "100k")
      (footprint "eagle-import:R0402")
      (libsource (lib "eagle-import") (part "R-US_R0402"))
    )
    (comp (ref "R27")
      (value "100k")
      (footprint "eagle-import:R0402")
      (libsource (lib "eagle-import") (part "R-US_R0402"))
    )
    (comp (ref "R28")
      (value "200k")
      (footprint "eagle-import:R0402")
      (libsource (lib "eagle-import") (part "R-US_R0402"))
    )
    (comp (ref "R29")
      (value "200k")
      (footprint "eagle-import:R0402")
      (libsource (lib "eagle-import") (part "R-US_R0402"))
    )
    (comp (ref "R30")
      (value "200k")
      (footprint "eagle-import:R0402")
      (libsource (lib "eagle-import") (part "R-US_R0402"))
    )
    (comp (ref "R31")
      (value "200k")
      (footprint "eagle-import:R0402")
      (libsource (lib "eagle-import") (part "R-US_R0402"))
    )
    (comp (ref "R32")
      (value "100k")
      (footprint "eagle-import:R0402")
      (libsource (lib "eagle-import") (part "R-US_R0402"))
    )
    (comp (ref "R33")
      (value "100k")
      (footprint "eagle-import:R0402")
      (libsource (lib "eagle-import") (part "R-US_R0402"))
    )
    (comp (ref "R34")
      (value "100k")
      (footprint "eagle-import:R0402")
      (libsource (lib "eagle-import") (part "R-US_R0402"))
    )
    (comp (ref "R35")
      (value "100k")
      (footprint "eagle-import:R0402")
      (libsource (lib "eagle-import") (part "R-US_R0402"))
    )
    (comp (ref "R39")
      (value "33k")
      (footprint "eagle-import:R0402")
      (libsource (lib "eagle-import") (part "R-US_R0402"))
    )
    (comp (ref "R40")
      (value "33k")
      (footprint "eagle-import:R0402")
      (libsource (lib "eagle-import") (part "R-US_R0402"))
    )
    (comp (ref "R41")
      (value "33k")
      (footprint "eagle-import:R0402")
      (libsource (lib "eagle-import") (part "R-US_R0402"))
    )
    (comp (ref "R42")
      (value "33k")
      (footprint "eagle-import:R0402")
      (libsource (lib "eagle-import") (part "R-US_R0402"))
    )
    (comp (ref "R57")
      (value "33k")
      (footprint "eagle-import:R0402")
      (libsource (lib "eagle-import") (part "R-US_R0402"))
    )
    (comp (ref "R58")
      (value "33k")
      (footprint "eagle-import:R0402")
      (libsource (lib "eagle-import") (part "R-US_R0402"))
    )
    (comp (ref "R59")
      (value "33k")
      (footprint "eagle-import:R0402")
      (libsource (lib "eagle-import") (part "R-US_R0402"))
    )
    (comp (ref "R64")
      (value "100k")
      (footprint "eagle-import:R0402")
      (libsource (lib "eagle-import") (part "R-US_R0402"))
    )
    (comp (ref "R65")
      (value "100k")
      (footprint "eagle-import:R0402")
      (libsource (lib "eagle-import") (part "R-US_R0402"))
    )
    (comp (ref "R66")
      (value "100k")
      (footprint "eagle-import:R0402")
      (libsource (lib "eagle-import") (part "R-US_R0402"))
    )
    (comp (ref "R70")
      (value "200k")
      (footprint "eagle-import:R0402")
      (libsource (lib "eagle-import") (part "R-US_R0402"))
    )
    (comp (ref "R71")
      (value "200k")
      (footprint "eagle-import:R0402")
      (libsource (lib "eagle-import") (part "R-US_R0402"))
    )
    (comp (ref "R72")
      (value "200k")
      (footprint "eagle-import:R0402")
      (libsource (lib "eagle-import") (part "R-US_R0402"))
    )
    (comp (ref "R76")
      (value "100k")
      (footprint "eagle-import:R0402")
      (libsource (lib "eagle-import") (part "R-US_R0402"))
    )
    (comp (ref "R77")
      (value "100k")
      (footprint "eagle-import:R0402")
      (libsource (lib "eagle-import") (part "R-US_R0402"))
    )
  )
  (nets
    (net (code "1") (name "+3V3") (class "Default")
      (node (ref "C1") (pin "1") (pinfunction "1_1") (pintype "passive"))
      (node (ref "C12") (pin "1") (pinfunction "1_1") (pintype "passive"))
      (node (ref "C13") (pin "1") (pinfunction "1_1") (pintype "passive"))
      (node (ref "C16") (pin "1") (pinfunction "1_1") (pintype "passive"))
      (node (ref "C19") (pin "1") (pinfunction "1_1") (pintype "passive"))
      (node (ref "C2") (pin "+") (pinfunction "+_+") (pintype "passive"))
      (node (ref "C21") (pin "1") (pinfunction "1_1") (pintype "passive"))
      (node (ref "D3") (pin "2") (pinfunction "C_2") (pintype "passive"))
      (node (ref "IC1") (pin "3") (pinfunction "VO_3") (pintype "passive"))
      (node (ref "IC2") (pin "1") (pinfunction "VBAT_1") (pintype "power_in"))
      (node (ref "IC2") (pin "19") (pinfunction "VDD_4_19") (pintype "power_in"))
      (node (ref "IC2") (pin "32") (pinfunction "VDD_1_32") (pintype "power_in"))
      (node (ref "IC2") (pin "48") (pinfunction "VDD_2_48") (pintype "power_in"))
      (node (ref "IC2") (pin "64") (pinfunction "VDD_3_64") (pintype "power_in"))
      (node (ref "IC4") (pin "12") (pinfunction "DVDD_12") (pintype "power_in"))
      (node (ref "R22") (pin "2") (pinfunction "2_2") (pintype "passive"))
      (node (ref "R23") (pin "2") (pinfunction "2_2") (pintype "passive"))
      (node (ref "R6") (pin "2") (pinfunction "2_2") (pintype "passive"))
    )
    (net (code "2") (name "+3V3_A") (class "Default")
      (node (ref "C10") (pin "1") (pinfunction "1_1") (pintype "passive"))
      (node (ref "C23") (pin "+") (pinfunction "+_+") (pintype "passive"))
      (node (ref "C26") (pin "1") (pinfunction "1_1") (pintype "passive"))
      (node (ref "C27") (pin "+") (pinfunction "+_+") (pintype "passive"))
      (node (ref "C46") (pin "1") (pinfunction "1_1") (pintype "passive"))
      (node (ref "C47") (pin "1") (pinfunction "1_1") (pintype "passive"))
      (node (ref "C9") (pin "1") (pinfunction "1_1") (pintype "passive"))
      (node (ref "IC2") (pin "13") (pinfunction "VDDA_13") (pintype "power_in"))
      (node (ref "IC3") (pin "1") (pinfunction "VO_1") (pintype "passive"))
      (node (ref "IC4") (pin "4") (pinfunction "AVDD_4") (pintype "power_in"))
      (node (ref "IC5") (pin "4") (pinfunction "V+_4") (pintype "power_in"))
      (node (ref "IC6") (pin "4") (pinfunction "V+_4") (pintype "power_in"))
      (node (ref "R13") (pin "P$1") (pinfunction "E_P$1") (pintype "passive"))
      (node (ref "R14") (pin "P$1") (pinfunction "E_P$1") (pintype "passive"))
      (node (ref "R16") (pin "P$1") (pinfunction "E_P$1") (pintype "passive"))
      (node (ref "R20") (pin "P$1") (pinfunction "E_P$1") (pintype "passive"))
      (node (ref "R21") (pin "P$1") (pinfunction "E_P$1") (pintype "passive"))
      (node (ref "R37") (pin "P$1") (pinfunction "E_P$1") (pintype "passive"))
      (node (ref "R38") (pin "P$1") (pinfunction "E_P$1") (pintype "passive"))
      (node (ref "R4") (pin "P$1") (pinfunction "E_P$1") (pintype "passive"))
    )
    (net (code "3") (name "ADC_DV_CV") (class "Default")
      (node (ref "C33") (pin "2") (pinfunction "2_2") (pintype "passive"))
      (node (ref "IC2") (pin "21") (pinfunction "PA5/SPI1_SCK/ADC5/DAC2_21") (pintype "bidirectional"))
      (node (ref "IC6") (pin "8") (pinfunction "OUT_8") (pintype "output"))
      (node (ref "R42") (pin "1") (pinfunction "1_1") (pintype "passive"))
    )
    (net (code "4") (name "ADC_DV_POT") (class "Default")
      (node (ref "C8") (pin "1") (pinfunction "1_1") (pintype "passive"))
      (node (ref "IC2") (pin "11") (pinfunction "PC3/SPI2_MOSI/I2S2_SD/ADC13_11") (pintype "bidirectional"))
      (node (ref "R4") (pin "P$2") (pinfunction "S_P$2") (pintype "passive"))
    )
    (net (code "5") (name "ADC_LENGTH_POT") (class "Default")
      (node (ref "C24") (pin "1") (pinfunction "1_1") (pintype "passive"))
      (node (ref "IC2") (pin "27") (pinfunction "PB1/ADC9/TIM3_CH4_27") (pintype "bidirectional"))
      (node (ref "R16") (pin "P$2") (pinfunction "S_P$2") (pintype "passive"))
    )
    (net (code "6") (name "ADC_T_BIAS_CV") (class "Default")
      (node (ref "C40") (pin "2") (pinfunction "2_2") (pintype "passive"))
      (node (ref "IC2") (pin "15") (pinfunction "PA1/USART2_RTS/UART4_RX/ADC1/TIM2_CH2_15") (pintype "bidirectional"))
      (node (ref "IC5") (pin "1") (pinfunction "OUT_1") (pintype "output"))
      (node (ref "R57") (pin "1") (pinfunction "1_1") (pintype "passive"))
    )
    (net (code "7") (name "ADC_T_BIAS_POT") (class "Default")
      (node (ref "C28") (pin "1") (pinfunction "1_1") (pintype "passive"))
      (node (ref "IC2") (pin "16") (pinfunction "PA2/USART2_TX/ADC2/TIM2_CH3_16") (pintype "bidirectional"))
      (node (ref "R20") (pin "P$2") (pinfunction "S_P$2") (pintype "passive"))
    )
    (net (code "8") (name "ADC_T_JITTER_CV") (class "Default")
      (node (ref "C42") (pin "2") (pinfunction "2_2") (pintype "passive"))
      (node (ref "IC2") (pin "20") (pinfunction "PA4/SPI1_NSS/SPI3_NSS/USART2_CK/I2S3_WS/ADC4/DAC1_20") (pintype "bidirectional"))
      (node (ref "IC6") (pin "7") (pinfunction "OUT_7") (pintype "output"))
      (node (ref "R59") (pin "1") (pinfunction "1_1") (pintype "passive"))
    )
    (net (code "9") (name "ADC_T_JITTER_POT") (class "Default")
      (node (ref "C38") (pin "1") (pinfunction "1_1") (pintype "passive"))
      (node (ref "IC2") (pin "25") (pinfunction "PC5/ADC15_25") (pintype "bidirectional"))
      (node (ref "R37") (pin "P$2") (pinfunction "S_P$2") (pintype "passive"))
    )
    (net (code "10") (name "ADC_T_RATE_CV") (class "Default")
      (node (ref "C41") (pin "2") (pinfunction "2_2") (pintype "passive"))
      (node (ref "IC2") (pin "17") (pinfunction "PA3/USART2_RX/ADC3/TIM2_CH4_17") (pintype "bidirectional"))
      (node (ref "IC6") (pin "1") (pinfunction "OUT_1") (pintype "output"))
      (node (ref "R58") (pin "1") (pinfunction "1_1") (pintype "passive"))
    )
    (net (code "11") (name "ADC_T_RATE_POT") (class "Default")
      (node (ref "C17") (pin "1") (pinfunction "1_1") (pintype "passive"))
      (node (ref "IC2") (pin "10") (pinfunction "PC2/SPI2_MISO/ADC12_10") (pintype "bidirectional"))
      (node (ref "R13") (pin "P$2") (pinfunction "S_P$2") (pintype "passive"))
    )
    (net (code "12") (name "ADC_X_BIAS_CV") (class "Default")
      (node (ref "C30") (pin "2") (pinfunction "2_2") (pintype "passive"))
      (node (ref "IC2") (pin "24") (pinfunction "PC4/ADC14_24") (pintype "bidirectional"))
      (node (ref "IC5") (pin "14") (pinfunction "OUT_14") (pintype "output"))
      (node (ref "R39") (pin "1") (pinfunction "1_1") (pintype "passive"))
    )
    (net (code "13") (name "ADC_X_BIAS_POT") (class "Default")
      (node (ref "C29") (pin "1") (pinfunction "1_1") (pintype "passive"))
      (node (ref "IC2") (pin "9") (pinfunction "PC1/ADC11_9") (pintype "bidirectional"))
      (node (ref "R21") (pin "P$2") (pinfunction "S_P$2") (pintype "passive"))
    )
    (net (code "14") (name "ADC_X_SPREAD_CV") (class "Default")
      (node (ref "C31") (pin "2") (pinfunction "2_2") (pintype "passive"))
      (node (ref "IC2") (pin "14") (pinfunction "PA0-WKUP/USART2_CTS/UART4_TX/ADC0/TIM2_CH1_ETR_14") (pintype "bidirectional"))
      (node (ref "IC2") (pin "23") (pinfunction "PA7/SPI1_MOSI/ADC7/TIM3_CH2_23") (pintype "bidirectional"))
      (node (ref "IC5") (pin "8") (pinfunction "OUT_8") (pintype "output"))
      (node (ref "R40") (pin "1") (pinfunction "1_1") (pintype "passive"))
    )
    (net (code "15") (name "ADC_X_SPREAD_POT") (class "Default")
      (node (ref "C18") (pin "1") (pinfunction "1_1") (pintype "passive"))
      (node (ref "IC2") (pin "8") (pinfunction "PC0/ADC10_8") (pintype "bidirectional"))
      (node (ref "R14") (pin "P$2") (pinfunction "S_P$2") (pintype "passive"))
    )
    (net (code "16") (name "ADC_X_STEPS_CV") (class "Default")
      (node (ref "C32") (pin "2") (pinfunction "2_2") (pintype "passive"))
      (node (ref "IC2") (pin "22") (pinfunction "PA6/SPI1_MISO/ADC6/TIM3_CH1_22") (pintype "bidirectional"))
      (node (ref "IC6") (pin "14") (pinfunction "OUT_14") (pintype "output"))
      (node (ref "R41") (pin "1") (pinfunction "1_1") (pintype "passive"))
    )
    (net (code "17") (name "ADC_X_STEPS_POT") (class "Default")
      (node (ref "C36") (pin "1") (pinfunction "1_1") (pintype "passive"))
      (node (ref "IC2") (pin "26") (pinfunction "PB0/ADC8/TIM3_CH3_26") (pintype "bidirectional"))
      (node (ref "R38") (pin "P$2") (pinfunction "S_P$2") (pintype "passive"))
    )
    (net (code "18") (name "AREF_-10") (class "Default")
      (node (ref "C52") (pin "1") (pinfunction "1_1") (pintype "passive"))
      (node (ref "IC8") (pin "2") (pinfunction "A_2") (pintype "passive"))
      (node (ref "R28") (pin "2") (pinfunction "2_2") (pintype "passive"))
      (node (ref "R29") (pin "2") (pinfunction "2_2") (pintype "passive"))
      (node (ref "R30") (pin "2") (pinfunction "2_2") (pintype "passive"))
      (node (ref "R31") (pin "2") (pinfunction "2_2") (pintype "passive"))
      (node (ref "R68") (pin "2") (pinfunction "2_2") (pintype "passive"))
      (node (ref "R70") (pin "2") (pinfunction "2_2") (pintype "passive"))
      (node (ref "R71") (pin "2") (pinfunction "2_2") (pintype "passive"))
      (node (ref "R72") (pin "2") (pinfunction "2_2") (pintype "passive"))
    )
    (net (code "19") (name "DAC_MOSI") (class "Default")
      (node (ref "IC2") (pin "53") (pinfunction "PC12/UART5_TX/I2S3_SD/USART3_CK_53") (pintype "bidirectional"))
      (node (ref "IC4") (pin "11") (pinfunction "IN_11") (pintype "input"))
    )
    (net (code "20") (name "DAC_SCK") (class "Default")
      (node (ref "IC2") (pin "51") (pinfunction "PC10/SPI3_SCK/I2S3_SCK/UART4_TX_51") (pintype "bidirectional"))
      (node (ref "IC4") (pin "10") (pinfunction "SCK_10") (pintype "input"))
    )
    (net (code "21") (name "DAC_SS") (class "Default")
      (node (ref "IC2") (pin "50") (pinfunction "PA15/JTDI/SPI3_NSS/I2S3_WS_50") (pintype "bidirectional"))
      (node (ref "IC4") (pin "9") (pinfunction "SYNC_9") (pintype "input"))
    )
    (net (code "22") (name "DAC_X_1") (class "Default")
      (node (ref "IC4") (pin "2") (pinfunction "OUTB_2") (pintype "output"))
      (node (ref "R47") (pin "2") (pinfunction "2_2") (pintype "passive"))
    )
    (net (code "23") (name "DAC_X_2") (class "Default")
      (node (ref "IC4") (pin "7") (pinfunction "OUTC_7") (pintype "output"))
      (node (ref "R48") (pin "2") (pinfunction "2_2") (pintype "passive"))
    )
    (net (code "24") (name "DAC_X_3") (class "Default")
      (node (ref "IC4") (pin "8") (pinfunction "OUTD_8") (pintype "output"))
      (node (ref "R53") (pin "2") (pinfunction "2_2") (pintype "passive"))
    )
    (net (code "25") (name "DAC_Y") (class "Default")
      (node (ref "IC4") (pin "1") (pinfunction "OUTA_1") (pintype "output"))
      (node (ref "R54") (pin "2") (pinfunction "2_2") (pintype "passive"))
    )
    (net (code "26") (name "DEPRECATED") (class "Default")
      (node (ref "IC5") (pin "6") (pinfunction "-IN_6") (pintype "input"))
      (node (ref "IC5") (pin "7") (pinfunction "OUT_7") (pintype "output"))
    )
    (net (code "27") (name "GATE_T_1") (class "Default")
      (node (ref "IC2") (pin "52") (pinfunction "PC11/UART4_RX/SPI3_MISO/USART3_RX_52") (pintype "bidirectional"))
      (node (ref "LED6") (pin "1") (pinfunction "1_1") (pintype "bidirectional"))
      (node (ref "R56") (pin "2") (pinfunction "2_2") (pintype "passive"))
    )
    (net (code "28") (name "GATE_T_2") (class "Default")
      (node (ref "IC2") (pin "44") (pinfunction "PA11/USART1_CTS/CANRX/USBDM/TIM1_CH4_44") (pintype "bidirectional"))
      (node (ref "LED7") (pin "1") (pinfunction "1_1") (pintype "bidirectional"))
      (node (ref "R55") (pin "2") (pinfunction "2_2") (pintype "passive"))
    )
    (net (code "29") (name "GATE_T_3") (class "Default")
      (node (ref "IC2") (pin "45") (pinfunction "PA12/USART1_RTS/CANTX/USBDP/TIM1_ETR_45") (pintype "bidirectional"))
      (node (ref "LED8") (pin "1") (pinfunction "1_1") (pintype "bidirectional"))
      (node (ref "R67") (pin "2") (pinfunction "2_2") (pintype "passive"))
    )
    (net (code "30") (name "GND") (class "Default")
      (node (ref "C1") (pin "2") (pinfunction "2_2") (pintype "passive"))
      (node (ref "C10") (pin "2") (pinfunction "2_2") (pintype "passive"))
      (node (ref "C11") (pin "-") (pinfunction "-_-") (pintype "passive"))
      (node (ref "C12") (pin "2") (pinfunction "2_2") (pintype "passive"))
      (node (ref "C13") (pin "2") (pinfunction "2_2") (pintype "passive"))
      (node (ref "C14") (pin "2") (pinfunction "2_2") (pintype "passive"))
      (node (ref "C15") (pin "2") (pinfunction "2_2") (pintype "passive"))
      (node (ref "C16") (pin "2") (pinfunction "2_2") (pintype "passive"))
      (node (ref "C17") (pin "2") (pinfunction "2_2") (pintype "passive"))
      (node (ref "C18") (pin "2") (pinfunction "2_2") (pintype "passive"))
      (node (ref "C19") (pin "2") (pinfunction "2_2") (pintype "passive"))
      (node (ref "C2") (pin "-") (pinfunction "-_-") (pintype "passive"))
      (node (ref "C20") (pin "2") (pinfunction "2_2") (pintype "passive"))
      (node (ref "C21") (pin "2") (pinfunction "2_2") (pintype "passive"))
      (node (ref "C22") (pin "+") (pinfunction "+_+") (pintype "passive"))
      (node (ref "C23") (pin "-") (pinfunction "-_-") (pintype "passive"))
      (node (ref "C24") (pin "2") (pinfunction "2_2") (pintype "passive"))
      (node (ref "C25") (pin "2") (pinfunction "2_2") (pintype "passive"))
      (node (ref "C26") (pin "2") (pinfunction "2_2") (pintype "passive"))
      (node (ref "C27") (pin "-") (pinfunction "-_-") (pintype "passive"))
      (node (ref "C28") (pin "2") (pinfunction "2_2") (pintype "passive"))
      (node (ref "C29") (pin "2") (pinfunction "2_2") (pintype "passive"))
      (node (ref "C3") (pin "2") (pinfunction "2_2") (pintype "passive"))
      (node (ref "C36") (pin "2") (pinfunction "2_2") (pintype "passive"))
      (node (ref "C37") (pin "1") (pinfunction "1_1") (pintype "passive"))
      (node (ref "C38") (pin "2") (pinfunction "2_2") (pintype "passive"))
      (node (ref "C39") (pin "2") (pinfunction "2_2") (pintype "passive"))
      (node (ref "C4") (pin "1") (pinfunction "1_1") (pintype "passive"))
      (node (ref "C45") (pin "2") (pinfunction "2_2") (pintype "passive"))
      (node (ref "C46") (pin "2") (pinfunction "2_2") (pintype "passive"))
      (node (ref "C47") (pin "2") (pinfunction "2_2") (pintype "passive"))
      (node (ref "C48") (pin "2") (pinfunction "2_2") (pintype "passive"))
      (node (ref "C49") (pin "1") (pinfunction "1_1") (pintype "passive"))
      (node (ref "C5") (pin "2") (pinfunction "2_2") (pintype "passive"))
      (node (ref "C50") (pin "2") (pinfunction "2_2") (pintype "passive"))
      (node (ref "C51") (pin "2") (pinfunction "2_2") (pintype "passive"))
      (node (ref "C52") (pin "2") (pinfunction "2_2") (pintype "passive"))
      (node (ref "C53") (pin "2") (pinfunction "2_2") (pintype "passive"))
      (node (ref "C54") (pin "2") (pinfunction "2_2") (pintype "passive"))
      (node (ref "C55") (pin "2") (pinfunction "2_2") (pintype "passive"))
      (node (ref "C56") (pin "2") (pinfunction "2_2") (pintype "passive"))
      (node (ref "C57") (pin "2") (pinfunction "2_2") (pintype "passive"))
      (node (ref "C58") (pin "2") (pinfunction "2_2") (pintype "passive"))
      (node (ref "C6") (pin "1") (pinfunction "1_1") (pintype "passive"))
      (node (ref "C7") (pin "2") (pinfunction "2_2") (pintype "passive"))
      (node (ref "C8") (pin "2") (pinfunction "2_2") (pintype "passive"))
      (node (ref "C9") (pin "2") (pinfunction "2_2") (pintype "passive"))
      (node (ref "D3") (pin "1") (pinfunction "A_1") (pintype "passive"))
      (node (ref "D4") (pin "A") (pinfunction "A_A") (pintype "passive"))
      (node (ref "D5") (pin "A") (pinfunction "A_A") (pintype "passive"))
      (node (ref "IC1") (pin "2") (pinfunction "GND_2") (pintype "passive"))
      (node (ref "IC2") (pin "12") (pinfunction "VSSA_12") (pintype "power_in"))
      (node (ref "IC2") (pin "18") (pinfunction "VSS_4_18") (pintype "power_in"))
      (node (ref "IC2") (pin "28") (pinfunction "PB2/BOOT1_28") (pintype "bidirectional"))
      (node (ref "IC2") (pin "60") (pinfunction "BOOT0_60") (pintype "bidirectional"))
      (node (ref "IC2") (pin "63") (pinfunction "VSS_3_63") (pintype "power_in"))
      (node (ref "IC3") (pin "2") (pinfunction "GND_2") (pintype "passive"))
      (node (ref "IC4") (pin "13") (pinfunction "A0_13") (pintype "input"))
      (node (ref "IC4") (pin "14") (pinfunction "A1_14") (pintype "input"))
      (node (ref "IC4") (pin "15") (pinfunction "ENABLE_15") (pintype "input"))
      (node (ref "IC4") (pin "16") (pinfunction "LDAC_16") (pintype "input"))
      (node (ref "IC4") (pin "5") (pinfunction "VREFL_5") (pintype "bidirectional"))
      (node (ref "IC4") (pin "6") (pinfunction "GND_6") (pintype "power_in"))
      (node (ref "IC5") (pin "10") (pinfunction "+IN_10") (pintype "input"))
      (node (ref "IC5") (pin "11") (pinfunction "V-_11") (pintype "power_in"))
      (node (ref "IC5") (pin "12") (pinfunction "+IN_12") (pintype "input"))
      (node (ref "IC5") (pin "3") (pinfunction "+IN_3") (pintype "input"))
      (node (ref "IC5") (pin "5") (pinfunction "+IN_5") (pintype "input"))
      (node (ref "IC6") (pin "10") (pinfunction "+IN_10") (pintype "input"))
      (node (ref "IC6") (pin "11") (pinfunction "V-_11") (pintype "power_in"))
      (node (ref "IC6") (pin "12") (pinfunction "+IN_12") (pintype "input"))
      (node (ref "IC6") (pin "3") (pinfunction "+IN_3") (pintype "input"))
      (node (ref "IC6") (pin "5") (pinfunction "+IN_5") (pintype "input"))
      (node (ref "IC8") (pin "1") (pinfunction "C_1") (pintype "passive"))
      (node (ref "IC9") (pin "11") (pinfunction "V-_11") (pintype "power_in"))
      (node (ref "IC9") (pin "5") (pinfunction "+IN_5") (pintype "input"))
      (node (ref "J1") (pin "P1") (pinfunction "1_P1") (pintype "passive"))
      (node (ref "J1") (pin "P2") (pinfunction "2_P2") (pintype "passive"))
      (node (ref "J10") (pin "P1") (pinfunction "1_P1") (pintype "passive"))
      (node (ref "J11") (pin "P1") (pinfunction "1_P1") (pintype "passive"))
      (node (ref "J12") (pin "P1") (pinfunction "1_P1") (pintype "passive"))
      (node (ref "J13") (pin "P1") (pinfunction "1_P1") (pintype "passive"))
      (node (ref "J14") (pin "P1") (pinfunction "1_P1") (pintype "passive"))
      (node (ref "J15") (pin "P1") (pinfunction "1_P1") (pintype "passive"))
      (node (ref "J16") (pin "P1") (pinfunction "1_P1") (pintype "passive"))
      (node (ref "J2") (pin "P1") (pinfunction "1_P1") (pintype "passive"))
      (node (ref "J2") (pin "P2") (pinfunction "2_P2") (pintype "passive"))
      (node (ref "J3") (pin "P1") (pinfunction "1_P1") (pintype "passive"))
      (node (ref "J4") (pin "P1") (pinfunction "1_P1") (pintype "passive"))
      (node (ref "J4") (pin "P2") (pinfunction "2_P2") (pintype "passive"))
      (node (ref "J5") (pin "P1") (pinfunction "1_P1") (pintype "passive"))
      (node (ref "J5") (pin "P2") (pinfunction "2_P2") (pintype "passive"))
      (node (ref "J6") (pin "P1") (pinfunction "1_P1") (pintype "passive"))
      (node (ref "J6") (pin "P2") (pinfunction "2_P2") (pintype "passive"))
      (node (ref "J7") (pin "P1") (pinfunction "1_P1") (pintype "passive"))
      (node (ref "J7") (pin "P2") (pinfunction "2_P2") (pintype "passive"))
      (node (ref "J8") (pin "P1") (pinfunction "1_P1") (pintype "passive"))
      (node (ref "J8") (pin "P2") (pinfunction "2_P2") (pintype "passive"))
      (node (ref "J9") (pin "P1") (pinfunction "1_P1") (pintype "passive"))
      (node (ref "JP1") (pin "1") (pinfunction "1_1") (pintype "passive"))
      (node (ref "JP4") (pin "3") (pinfunction "3_3") (pintype "passive"))
      (node (ref "JP4") (pin "4") (pinfunction "4_4") (pintype "passive"))
      (node (ref "JP4") (pin "5") (pinfunction "5_5") (pintype "passive"))
      (node (ref "JP4") (pin "6") (pinfunction "6_6") (pintype "passive"))
      (node (ref "JP4") (pin "7") (pinfunction "7_7") (pintype "passive"))
      (node (ref "JP4") (pin "8") (pinfunction "8_8") (pintype "passive"))
      (node (ref "LED1") (pin "2") (pinfunction "C_2") (pintype "bidirectional"))
      (node (ref "LED2") (pin "2") (pinfunction "C_2") (pintype "bidirectional"))
      (node (ref "LED3") (pin "2") (pinfunction "C_2") (pintype "bidirectional"))
      (node (ref "LED4") (pin "2") (pinfunction "C_2") (pintype "bidirectional"))
      (node (ref "LED5") (pin "2") (pinfunction "C_2") (pintype "bidirectional"))
      (node (ref "Q1") (pin "2") (pinfunction "LID1_2") (pintype "power_in"))
      (node (ref "Q1") (pin "4") (pinfunction "LID2_4") (pintype "power_in"))
      (node (ref "Q2") (pin "E") (pinfunction "E_E") (pintype "passive"))
      (node (ref "Q3") (pin "E") (pinfunction "E_E") (pintype "passive"))
      (node (ref "R13") (pin "P$3") (pinfunction "A_P$3") (pintype "passive"))
      (node (ref "R14") (pin "P$3") (pinfunction "A_P$3") (pintype "passive"))
      (node (ref "R16") (pin "P$3") (pinfunction "A_P$3") (pintype "passive"))
      (node (ref "R20") (pin "P$3") (pinfunction "A_P$3") (pintype "passive"))
      (node (ref "R21") (pin "P$3") (pinfunction "A_P$3") (pintype "passive"))
      (node (ref "R24") (pin "1") (pinfunction "1_1") (pintype "passive"))
      (node (ref "R25") (pin "1") (pinfunction "1_1") (pintype "passive"))
      (node (ref "R37") (pin "P$3") (pinfunction "A_P$3") (pintype "passive"))
      (node (ref "R38") (pin "P$3") (pinfunction "A_P$3") (pintype "passive"))
      (node (ref "R4") (pin "P$3") (pinfunction "A_P$3") (pintype "passive"))
      (node (ref "R49") (pin "2") (pinfunction "2_2") (pintype "passive"))
      (node (ref "R50") (pin "2") (pinfunction "2_2") (pintype "passive"))
      (node (ref "R73") (pin "1") (pinfunction "1_1") (pintype "passive"))
      (node (ref "R75") (pin "2") (pinfunction "2_2") (pintype "passive"))
      (node (ref "R78") (pin "2") (pinfunction "2_2") (pintype "passive"))
      (node (ref "R79") (pin "2") (pinfunction "2_2") (pintype "passive"))
      (node (ref "R80") (pin "2") (pinfunction "2_2") (pintype "passive"))
      (node (ref "R81") (pin "2") (pinfunction "2_2") (pintype "passive"))
      (node (ref "R82") (pin "1") (pinfunction "1_1") (pintype "passive"))
      (node (ref "R83") (pin "1") (pinfunction "1_1") (pintype "passive"))
      (node (ref "R84") (pin "1") (pinfunction "1_1") (pintype "passive"))
      (node (ref "SW1") (pin "L2") (pinfunction "L2_L2") (pintype "passive"))
      (node (ref "SW1") (pin "P3") (pinfunction "A3_P3") (pintype "passive"))
      (node (ref "SW1") (pin "P6") (pinfunction "B3_P6") (pintype "passive"))
      (node (ref "SW2") (pin "L2") (pinfunction "L2_L2") (pintype "passive"))
      (node (ref "SW2") (pin "P3") (pinfunction "A3_P3") (pintype "passive"))
      (node (ref "SW2") (pin "P6") (pinfunction "B3_P6") (pintype "passive"))
      (node (ref "SW3") (pin "1") (pinfunction "1_1") (pintype "passive"))
      (node (ref "SW3") (pin "2") (pinfunction "2_2") (pintype "passive"))
      (node (ref "SW4") (pin "1") (pinfunction "1_1") (pintype "passive"))
      (node (ref "SW4") (pin "2") (pinfunction "2_2") (pintype "passive"))
      (node (ref "SW5") (pin "1") (pinfunction "1_1") (pintype "passive"))
      (node (ref "SW5") (pin "2") (pinfunction "2_2") (pintype "passive"))
      (node (ref "SW6") (pin "1") (pinfunction "1_1") (pintype "passive"))
      (node (ref "SW6") (pin "2") (pinfunction "2_2") (pintype "passive"))
      (node (ref "SW7") (pin "1") (pinfunction "1_1") (pintype "passive"))
      (node (ref "SW7") (pin "2") (pinfunction "2_2") (pintype "passive"))
    )
    (net (code "31") (name "LED_T_DV") (class "Default")
      (node (ref "IC2") (pin "29") (pinfunction "PB10/SPI2_SCK/I2S_SCK/I2C2_SCL/USART3_TX_29") (pintype "bidirectional"))
      (node (ref "R1") (pin "1") (pinfunction "1_1") (pintype "passive"))
    )
    (net (code "32") (name "LED_T_MODE_G") (class "Default")
      (node (ref "IC2") (pin "33") (pinfunction "PB12/SPI2_NSS/I2S2_WS/I2C2_SMBA/USART3_CK/TIM1_BKIN_33") (pintype "bidirectional"))
      (node (ref "R10") (pin "1") (pinfunction "1_1") (pintype "passive"))
    )
    (net (code "33") (name "LED_T_MODE_R") (class "Default")
      (node (ref "IC2") (pin "34") (pinfunction "PB13/SPI2_SCK/I2S2_SCK/USART3_CTS/TIM1_CH1N_34") (pintype "bidirectional"))
      (node (ref "R9") (pin "1") (pinfunction "1_1") (pintype "passive"))
    )
    (net (code "34") (name "LED_T_RANGE_G") (class "Default")
      (node (ref "IC2") (pin "37") (pinfunction "PC6/I2S2_MCK_37") (pintype "bidirectional"))
      (node (ref "R18") (pin "1") (pinfunction "1_1") (pintype "passive"))
    )
    (net (code "35") (name "LED_T_RANGE_R") (class "Default")
      (node (ref "IC2") (pin "38") (pinfunction "PC7/I2S3_MCK_38") (pintype "bidirectional"))
      (node (ref "R19") (pin "1") (pinfunction "1_1") (pintype "passive"))
    )
    (net (code "36") (name "LED_X_DV") (class "Default")
      (node (ref "IC2") (pin "62") (pinfunction "PB9/SPI2_NSS/I2S2_WS/I2C1_SDA/TIM4_CH4_62") (pintype "bidirectional"))
      (node (ref "R5") (pin "1") (pinfunction "1_1") (pintype "passive"))
    )
    (net (code "37") (name "LED_X_EXT_G") (class "Default")
      (node (ref "IC2") (pin "55") (pinfunction "PB3/JTDO/SPI3_SCK/I2S3_SCK_55") (pintype "bidirectional"))
      (node (ref "R36") (pin "1") (pinfunction "1_1") (pintype "passive"))
    )
    (net (code "38") (name "LED_X_MODE_G") (class "Default")
      (node (ref "IC2") (pin "59") (pinfunction "PB7/I2C1_SDA/TIM4_CH2/USART1_RX_59") (pintype "bidirectional"))
      (node (ref "R12") (pin "1") (pinfunction "1_1") (pintype "passive"))
    )
    (net (code "39") (name "LED_X_MODE_R") (class "Default")
      (node (ref "IC2") (pin "61") (pinfunction "PB8/TIM4_CH3/I2C1_SCL_61") (pintype "bidirectional"))
      (node (ref "R11") (pin "1") (pinfunction "1_1") (pintype "passive"))
    )
    (net (code "40") (name "LED_X_RANGE_G") (class "Default")
      (node (ref "IC2") (pin "57") (pinfunction "PB5/I2C1_SMBA/SPI1_MOSI/SPI3_MOSI/I2S3_SD_57") (pintype "bidirectional"))
      (node (ref "R17") (pin "1") (pinfunction "1_1") (pintype "passive"))
    )
    (net (code "41") (name "LED_X_RANGE_R") (class "Default")
      (node (ref "IC2") (pin "56") (pinfunction "PB4/NJTRST/SPI3_MISO/SPI1_MISO_56") (pintype "bidirectional"))
      (node (ref "R15") (pin "1") (pinfunction "1_1") (pintype "passive"))
    )
    (net (code "42") (name "NORMALIZATION_PROBE") (class "Default")
      (node (ref "D3") (pin "3") (pinfunction "AC_3") (pintype "passive"))
      (node (ref "IC2") (pin "39") (pinfunction "PC8_39") (pintype "bidirectional"))
      (node (ref "R76") (pin "1") (pinfunction "1_1") (pintype "passive"))
      (node (ref "R77") (pin "1") (pinfunction "1_1") (pintype "passive"))
    )
    (net (code "43") (name "Net-(C5-Pad1)") (class "Default")
      (node (ref "C5") (pin "1") (pinfunction "1_1") (pintype "passive"))
      (node (ref "D1") (pin "C") (pinfunction "C_C") (pintype "passive"))
      (node (ref "L1") (pin "1") (pinfunction "1_1") (pintype "passive"))
      (node (ref "L2") (pin "2") (pinfunction "2_2") (pintype "passive"))
      (node (ref "L3") (pin "2") (pinfunction "2_2") (pintype "passive"))
    )
    (net (code "44") (name "Net-(C6-Pad2)") (class "Default")
      (node (ref "C6") (pin "2") (pinfunction "2_2") (pintype "passive"))
      (node (ref "Q1") (pin "1") (pinfunction "1_1") (pintype "passive"))
      (node (ref "R7") (pin "2") (pinfunction "2_2") (pintype "passive"))
    )
    (net (code "45") (name "Net-(D1-PadA)") (class "Default")
      (node (ref "D1") (pin "A") (pinfunction "A_A") (pintype "passive"))
      (node (ref "JP4") (pin "10") (pinfunction "10_10") (pintype "passive"))
      (node (ref "JP4") (pin "9") (pinfunction "9_9") (pintype "passive"))
    )
    (net (code "46") (name "Net-(D2-PadA)") (class "Default")
      (node (ref "D2") (pin "A") (pinfunction "A_A") (pintype "passive"))
      (node (ref "L4") (pin "2") (pinfunction "2_2") (pintype "passive"))
    )
    (net (code "47") (name "Net-(D2-PadC)") (class "Default")
      (node (ref "D2") (pin "C") (pinfunction "C_C") (pintype "passive"))
      (node (ref "JP4") (pin "1") (pinfunction "1_1") (pintype "passive"))
      (node (ref "JP4") (pin "2") (pinfunction "2_2") (pintype "passive"))
    )
    (net (code "48") (name "Net-(D4-PadC)") (class "Default")
      (node (ref "D4") (pin "C") (pinfunction "C_C") (pintype "passive"))
      (node (ref "Q2") (pin "B") (pinfunction "B_B") (pintype "passive"))
      (node (ref "R24") (pin "2") (pinfunction "2_2") (pintype "passive"))
      (node (ref "R26") (pin "2") (pinfunction "2_2") (pintype "passive"))
    )
    (net (code "49") (name "Net-(D5-PadC)") (class "Default")
      (node (ref "D5") (pin "C") (pinfunction "C_C") (pintype "passive"))
      (node (ref "Q3") (pin "B") (pinfunction "B_B") (pintype "passive"))
      (node (ref "R25") (pin "2") (pinfunction "2_2") (pintype "passive"))
      (node (ref "R27") (pin "2") (pinfunction "2_2") (pintype "passive"))
    )
    (net (code "50") (name "Net-(IC1-VI)") (class "Default")
      (node (ref "C3") (pin "1") (pinfunction "1_1") (pintype "passive"))
      (node (ref "IC1") (pin "1") (pinfunction "VI_1") (pintype "input"))
      (node (ref "L1") (pin "2") (pinfunction "2_2") (pintype "passive"))
    )
    (net (code "51") (name "Net-(IC2-PD0{slash}OSC_IN)") (class "Default")
      (node (ref "IC2") (pin "5") (pinfunction "PD0/OSC_IN_5") (pintype "bidirectional"))
      (node (ref "R8") (pin "1") (pinfunction "1_1") (pintype "passive"))
    )
    (net (code "52") (name "Net-(IC2-PD1{slash}OSC_OUT)") (class "Default")
      (node (ref "IC2") (pin "6") (pinfunction "PD1/OSC_OUT_6") (pintype "bidirectional"))
      (node (ref "R7") (pin "1") (pinfunction "1_1") (pintype "passive"))
    )
    (net (code "53") (name "Net-(IC2-VCAP_1)") (class "Default")
      (node (ref "C15") (pin "1") (pinfunction "1_1") (pintype "passive"))
      (node (ref "IC2") (pin "31") (pinfunction "VCAP_1_31") (pintype "power_in"))
    )
    (net (code "54") (name "Net-(IC2-VCAP_2)") (class "Default")
      (node (ref "C20") (pin "1") (pinfunction "1_1") (pintype "passive"))
      (node (ref "IC2") (pin "47") (pinfunction "VCAP_2_47") (pintype "power_in"))
    )
    (net (code "55") (name "Net-(IC3-VI)") (class "Default")
      (node (ref "C14") (pin "1") (pinfunction "1_1") (pintype "passive"))
      (node (ref "IC3") (pin "3") (pinfunction "VI_3") (pintype "input"))
      (node (ref "L3") (pin "1") (pinfunction "1_1") (pintype "passive"))
    )
    (net (code "56") (name "Net-(IC5A--IN)") (class "Default")
      (node (ref "C40") (pin "1") (pinfunction "1_1") (pintype "passive"))
      (node (ref "IC5") (pin "2") (pinfunction "-IN_2") (pintype "input"))
      (node (ref "R57") (pin "2") (pinfunction "2_2") (pintype "passive"))
      (node (ref "R64") (pin "1") (pinfunction "1_1") (pintype "passive"))
      (node (ref "R70") (pin "1") (pinfunction "1_1") (pintype "passive"))
    )
    (net (code "57") (name "Net-(IC5C--IN)") (class "Default")
      (node (ref "C31") (pin "1") (pinfunction "1_1") (pintype "passive"))
      (node (ref "IC5") (pin "9") (pinfunction "-IN_9") (pintype "input"))
      (node (ref "R28") (pin "1") (pinfunction "1_1") (pintype "passive"))
      (node (ref "R34") (pin "1") (pinfunction "1_1") (pintype "passive"))
      (node (ref "R40") (pin "2") (pinfunction "2_2") (pintype "passive"))
    )
    (net (code "58") (name "Net-(IC5D--IN)") (class "Default")
      (node (ref "C30") (pin "1") (pinfunction "1_1") (pintype "passive"))
      (node (ref "IC5") (pin "13") (pinfunction "-IN_13") (pintype "input"))
      (node (ref "R30") (pin "1") (pinfunction "1_1") (pintype "passive"))
      (node (ref "R33") (pin "1") (pinfunction "1_1") (pintype "passive"))
      (node (ref "R39") (pin "2") (pinfunction "2_2") (pintype "passive"))
    )
    (net (code "59") (name "Net-(IC6A--IN)") (class "Default")
      (node (ref "C41") (pin "1") (pinfunction "1_1") (pintype "passive"))
      (node (ref "IC6") (pin "2") (pinfunction "-IN_2") (pintype "input"))
      (node (ref "R58") (pin "2") (pinfunction "2_2") (pintype "passive"))
      (node (ref "R65") (pin "1") (pinfunction "1_1") (pintype "passive"))
      (node (ref "R71") (pin "1") (pinfunction "1_1") (pintype "passive"))
    )
    (net (code "60") (name "Net-(IC6B--IN)") (class "Default")
      (node (ref "C42") (pin "1") (pinfunction "1_1") (pintype "passive"))
      (node (ref "IC6") (pin "6") (pinfunction "-IN_6") (pintype "input"))
      (node (ref "R59") (pin "2") (pinfunction "2_2") (pintype "passive"))
      (node (ref "R66") (pin "1") (pinfunction "1_1") (pintype "passive"))
      (node (ref "R72") (pin "1") (pinfunction "1_1") (pintype "passive"))
    )
    (net (code "61") (name "Net-(IC6C--IN)") (class "Default")
      (node (ref "C33") (pin "1") (pinfunction "1_1") (pintype "passive"))
      (node (ref "IC6") (pin "9") (pinfunction "-IN_9") (pintype "input"))
      (node (ref "R31") (pin "1") (pinfunction "1_1") (pintype "passive"))
      (node (ref "R32") (pin "1") (pinfunction "1_1") (pintype "passive"))
      (node (ref "R42") (pin "2") (pinfunction "2_2") (pintype "passive"))
    )
    (net (code "62") (name "Net-(IC6D--IN)") (class "Default")
      (node (ref "C32") (pin "1") (pinfunction "1_1") (pintype "passive"))
      (node (ref "IC6") (pin "13") (pinfunction "-IN_13") (pintype "input"))
      (node (ref "R29") (pin "1") (pinfunction "1_1") (pintype "passive"))
      (node (ref "R35") (pin "1") (pinfunction "1_1") (pintype "passive"))
      (node (ref "R41") (pin "2") (pinfunction "2_2") (pintype "passive"))
    )
    (net (code "63") (name "Net-(IC7A--IN)") (class "Default")
      (node (ref "C34") (pin "1") (pinfunction "1_1") (pintype "passive"))
      (node (ref "IC7") (pin "2") (pinfunction "-IN_2") (pintype "input"))
      (node (ref "R43") (pin "2") (pinfunction "2_2") (pintype "passive"))
      (node (ref "R47") (pin "1") (pinfunction "1_1") (pintype "passive"))
    )
    (net (code "64") (name "Net-(IC7B--IN)") (class "Default")
      (node (ref "C43") (pin "1") (pinfunction "1_1") (pintype "passive"))
      (node (ref "IC7") (pin "6") (pinfunction "-IN_6") (pintype "input"))
      (node (ref "R54") (pin "1") (pinfunction "1_1") (pintype "passive"))
      (node (ref "R60") (pin "2") (pinfunction "2_2") (pintype "passive"))
    )
    (net (code "65") (name "Net-(IC7C--IN)") (class "Default")
      (node (ref "C44") (pin "1") (pinfunction "1_1") (pintype "passive"))
      (node (ref "IC7") (pin "9") (pinfunction "-IN_9") (pintype "input"))
      (node (ref "R53") (pin "1") (pinfunction "1_1") (pintype "passive"))
      (node (ref "R61") (pin "2") (pinfunction "2_2") (pintype "passive"))
    )
    (net (code "66") (name "Net-(IC7D--IN)") (class "Default")
      (node (ref "C35") (pin "1") (pinfunction "1_1") (pintype "passive"))
      (node (ref "IC7") (pin "13") (pinfunction "-IN_13") (pintype "input"))
      (node (ref "R44") (pin "2") (pinfunction "2_2") (pintype "passive"))
      (node (ref "R48") (pin "1") (pinfunction "1_1") (pintype "passive"))
    )
    (net (code "67") (name "Net-(IC9A-+IN)") (class "Default")
      (node (ref "IC9") (pin "3") (pinfunction "+IN_3") (pintype "input"))
      (node (ref "R56") (pin "1") (pinfunction "1_1") (pintype "passive"))
    )
    (net (code "68") (name "Net-(IC9A--IN)") (class "Default")
      (node (ref "IC9") (pin "2") (pinfunction "-IN_2") (pintype "input"))
      (node (ref "R50") (pin "1") (pinfunction "1_1") (pintype "passive"))
      (node (ref "R51") (pin "2") (pinfunction "2_2") (pintype "passive"))
    )
    (net (code "69") (name "Net-(IC9A-OUT)") (class "Default")
      (node (ref "IC9") (pin "1") (pinfunction "OUT_1") (pintype "output"))
      (node (ref "R51") (pin "1") (pinfunction "1_1") (pintype "passive"))
      (node (ref "R85") (pin "2") (pinfunction "2_2") (pintype "passive"))
    )
    (net (code "70") (name "Net-(IC9B--IN)") (class "Default")
      (node (ref "IC9") (pin "6") (pinfunction "-IN_6") (pintype "input"))
      (node (ref "IC9") (pin "7") (pinfunction "OUT_7") (pintype "output"))
    )
    (net (code "71") (name "Net-(IC9C-+IN)") (class "Default")
      (node (ref "IC9") (pin "10") (pinfunction "+IN_10") (pintype "input"))
      (node (ref "R67") (pin "1") (pinfunction "1_1") (pintype "passive"))
    )
    (net (code "72") (name "Net-(IC9C--IN)") (class "Default")
      (node (ref "IC9") (pin "9") (pinfunction "-IN_9") (pintype "input"))
      (node (ref "R69") (pin "2") (pinfunction "2_2") (pintype "passive"))
      (node (ref "R75") (pin "1") (pinfunction "1_1") (pintype "passive"))
    )
    (net (code "73") (name "Net-(IC9C-OUT)") (class "Default")
      (node (ref "IC9") (pin "8") (pinfunction "OUT_8") (pintype "output"))
      (node (ref "R69") (pin "1") (pinfunction "1_1") (pintype "passive"))
      (node (ref "R87") (pin "2") (pinfunction "2_2") (pintype "passive"))
    )
    (net (code "74") (name "Net-(IC9D-+IN)") (class "Default")
      (node (ref "IC9") (pin "12") (pinfunction "+IN_12") (pintype "input"))
      (node (ref "R55") (pin "1") (pinfunction "1_1") (pintype "passive"))
    )
    (net (code "75") (name "Net-(IC9D--IN)") (class "Default")
      (node (ref "IC9") (pin "13") (pinfunction "-IN_13") (pintype "input"))
      (node (ref "R49") (pin "1") (pinfunction "1_1") (pintype "passive"))
      (node (ref "R52") (pin "2") (pinfunction "2_2") (pintype "passive"))
    )
    (net (code "76") (name "Net-(IC9D-OUT)") (class "Default")
      (node (ref "IC9") (pin "14") (pinfunction "OUT_14") (pintype "output"))
      (node (ref "R52") (pin "1") (pinfunction "1_1") (pintype "passive"))
      (node (ref "R86") (pin "2") (pinfunction "2_2") (pintype "passive"))
    )
    (net (code "77") (name "Net-(IC10A-+IN)") (class "Default")
      (node (ref "C34") (pin "2") (pinfunction "2_2") (pintype "passive"))
      (node (ref "IC10") (pin "3") (pinfunction "+IN_3") (pintype "input"))
      (node (ref "IC7") (pin "1") (pinfunction "OUT_1") (pintype "output"))
      (node (ref "R45") (pin "2") (pinfunction "2_2") (pintype "passive"))
    )
    (net (code "78") (name "Net-(IC10A--IN)") (class "Default")
      (node (ref "IC10") (pin "2") (pinfunction "-IN_2") (pintype "input"))
      (node (ref "LED10") (pin "2") (pinfunction "2_2") (pintype "bidirectional"))
      (node (ref "R79") (pin "1") (pinfunction "1_1") (pintype "passive"))
    )
    (net (code "79") (name "Net-(IC10A-OUT)") (class "Default")
      (node (ref "IC10") (pin "1") (pinfunction "OUT_1") (pintype "output"))
      (node (ref "LED10") (pin "1") (pinfunction "1_1") (pintype "bidirectional"))
    )
    (net (code "80") (name "Net-(IC10B-+IN)") (class "Default")
      (node (ref "C43") (pin "2") (pinfunction "2_2") (pintype "passive"))
      (node (ref "IC10") (pin "5") (pinfunction "+IN_5") (pintype "input"))
      (node (ref "IC7") (pin "7") (pinfunction "OUT_7") (pintype "output"))
      (node (ref "R62") (pin "2") (pinfunction "2_2") (pintype "passive"))
    )
    (net (code "81") (name "Net-(IC10B--IN)") (class "Default")
      (node (ref "IC10") (pin "6") (pinfunction "-IN_6") (pintype "input"))
      (node (ref "LED9") (pin "2") (pinfunction "2_2") (pintype "bidirectional"))
      (node (ref "R78") (pin "1") (pinfunction "1_1") (pintype "passive"))
    )
    (net (code "82") (name "Net-(IC10B-OUT)") (class "Default")
      (node (ref "IC10") (pin "7") (pinfunction "OUT_7") (pintype "output"))
      (node (ref "LED9") (pin "1") (pinfunction "1_1") (pintype "bidirectional"))
    )
    (net (code "83") (name "Net-(IC10C-+IN)") (class "Default")
      (node (ref "C44") (pin "2") (pinfunction "2_2") (pintype "passive"))
      (node (ref "IC10") (pin "10") (pinfunction "+IN_10") (pintype "input"))
      (node (ref "IC7") (pin "8") (pinfunction "OUT_8") (pintype "output"))
      (node (ref "R63") (pin "2") (pinfunction "2_2") (pintype "passive"))
    )
    (net (code "84") (name "Net-(IC10C--IN)") (class "Default")
      (node (ref "IC10") (pin "9") (pinfunction "-IN_9") (pintype "input"))
      (node (ref "LED12") (pin "2") (pinfunction "2_2") (pintype "bidirectional"))
      (node (ref "R81") (pin "1") (pinfunction "1_1") (pintype "passive"))
    )
    (net (code "85") (name "Net-(IC10C-OUT)") (class "Default")
      (node (ref "IC10") (pin "8") (pinfunction "OUT_8") (pintype "output"))
      (node (ref "LED12") (pin "1") (pinfunction "1_1") (pintype "bidirectional"))
    )
    (net (code "86") (name "Net-(IC10D-+IN)") (class "Default")
      (node (ref "C35") (pin "2") (pinfunction "2_2") (pintype "passive"))
      (node (ref "IC10") (pin "12") (pinfunction "+IN_12") (pintype "input"))
      (node (ref "IC7") (pin "14") (pinfunction "OUT_14") (pintype "output"))
      (node (ref "R46") (pin "2") (pinfunction "2_2") (pintype "passive"))
    )
    (net (code "87") (name "Net-(IC10D--IN)") (class "Default")
      (node (ref "IC10") (pin "13") (pinfunction "-IN_13") (pintype "input"))
      (node (ref "LED11") (pin "2") (pinfunction "2_2") (pintype "bidirectional"))
      (node (ref "R80") (pin "1") (pinfunction "1_1") (pintype "passive"))
    )
    (net (code "88") (name "Net-(IC10D-OUT)") (class "Default")
      (node (ref "IC10") (pin "14") (pinfunction "OUT_14") (pintype "output"))
      (node (ref "LED11") (pin "1") (pinfunction "1_1") (pintype "bidirectional"))
    )
    (net (code "89") (name "Net-(J1-3)") (class "Default")
      (node (ref "C53") (pin "1") (pinfunction "1_1") (pintype "passive"))
      (node (ref "J1") (pin "P3") (pinfunction "3_P3") (pintype "passive"))
      (node (ref "R64") (pin "2") (pinfunction "2_2") (pintype "passive"))
    )
    (net (code "90") (name "Net-(J2-3)") (class "Default")
      (node (ref "C45") (pin "1") (pinfunction "1_1") (pintype "passive"))
      (node (ref "J2") (pin "P3") (pinfunction "3_P3") (pintype "passive"))
      (node (ref "R33") (pin "2") (pinfunction "2_2") (pintype "passive"))
    )
    (net (code "91") (name "Net-(J3-2)") (class "Default")
      (node (ref "J3") (pin "P2") (pinfunction "2_P2") (pintype "passive"))
      (node (ref "R76") (pin "2") (pinfunction "2_2") (pintype "passive"))
    )
    (net (code "92") (name "Net-(J3-3)") (class "Default")
      (node (ref "J3") (pin "P3") (pinfunction "3_P3") (pintype "passive"))
      (node (ref "R26") (pin "1") (pinfunction "1_1") (pintype "passive"))
    )
    (net (code "93") (name "Net-(J4-3)") (class "Default")
      (node (ref "C56") (pin "1") (pinfunction "1_1") (pintype "passive"))
      (node (ref "J4") (pin "P3") (pinfunction "3_P3") (pintype "passive"))
      (node (ref "R65") (pin "2") (pinfunction "2_2") (pintype "passive"))
    )
    (net (code "94") (name "Net-(J5-3)") (class "Default")
      (node (ref "C58") (pin "1") (pinfunction "1_1") (pintype "passive"))
      (node (ref "J5") (pin "P3") (pinfunction "3_P3") (pintype "passive"))
      (node (ref "R66") (pin "2") (pinfunction "2_2") (pintype "passive"))
    )
    (net (code "95") (name "Net-(J6-3)") (class "Default")
      (node (ref "C54") (pin "1") (pinfunction "1_1") (pintype "passive"))
      (node (ref "J6") (pin "P3") (pinfunction "3_P3") (pintype "passive"))
      (node (ref "R32") (pin "2") (pinfunction "2_2") (pintype "passive"))
    )
    (net (code "96") (name "Net-(J7-3)") (class "Default")
      (node (ref "C55") (pin "1") (pinfunction "1_1") (pintype "passive"))
      (node (ref "J7") (pin "P3") (pinfunction "3_P3") (pintype "passive"))
      (node (ref "R35") (pin "2") (pinfunction "2_2") (pintype "passive"))
    )
    (net (code "97") (name "Net-(J8-3)") (class "Default")
      (node (ref "C57") (pin "1") (pinfunction "1_1") (pintype "passive"))
      (node (ref "J8") (pin "P3") (pinfunction "3_P3") (pintype "passive"))
      (node (ref "R34") (pin "2") (pinfunction "2_2") (pintype "passive"))
    )
    (net (code "98") (name "Net-(J9-2)") (class "Default")
      (node (ref "J9") (pin "P2") (pinfunction "2_P2") (pintype "passive"))
      (node (ref "R77") (pin "2") (pinfunction "2_2") (pintype "passive"))
    )
    (net (code "99") (name "Net-(J9-3)") (class "Default")
      (node (ref "J9") (pin "P3") (pinfunction "3_P3") (pintype "passive"))
      (node (ref "R27") (pin "1") (pinfunction "1_1") (pintype "passive"))
    )
    (net (code "100") (name "Net-(J10-3)") (class "Default")
      (node (ref "J10") (pin "P3") (pinfunction "3_P3") (pintype "passive"))
      (node (ref "R85") (pin "1") (pinfunction "1_1") (pintype "passive"))
    )
    (net (code "101") (name "Net-(J11-3)") (class "Default")
      (node (ref "J11") (pin "P3") (pinfunction "3_P3") (pintype "passive"))
      (node (ref "R86") (pin "1") (pinfunction "1_1") (pintype "passive"))
    )
    (net (code "102") (name "Net-(J12-3)") (class "Default")
      (node (ref "J12") (pin "P3") (pinfunction "3_P3") (pintype "passive"))
      (node (ref "R87") (pin "1") (pinfunction "1_1") (pintype "passive"))
    )
    (net (code "103") (name "Net-(J13-3)") (class "Default")
      (node (ref "J13") (pin "P3") (pinfunction "3_P3") (pintype "passive"))
      (node (ref "R60") (pin "1") (pinfunction "1_1") (pintype "passive"))
      (node (ref "R62") (pin "1") (pinfunction "1_1") (pintype "passive"))
    )
    (net (code "104") (name "Net-(J14-3)") (class "Default")
      (node (ref "J14") (pin "P3") (pinfunction "3_P3") (pintype "passive"))
      (node (ref "R43") (pin "1") (pinfunction "1_1") (pintype "passive"))
      (node (ref "R45") (pin "1") (pinfunction "1_1") (pintype "passive"))
    )
    (net (code "105") (name "Net-(J15-3)") (class "Default")
      (node (ref "J15") (pin "P3") (pinfunction "3_P3") (pintype "passive"))
      (node (ref "R44") (pin "1") (pinfunction "1_1") (pintype "passive"))
      (node (ref "R46") (pin "1") (pinfunction "1_1") (pintype "passive"))
    )
    (net (code "106") (name "Net-(J16-3)") (class "Default")
      (node (ref "J16") (pin "P3") (pinfunction "3_P3") (pintype "passive"))
      (node (ref "R61") (pin "1") (pinfunction "1_1") (pintype "passive"))
      (node (ref "R63") (pin "1") (pinfunction "1_1") (pintype "passive"))
    )
    (net (code "107") (name "Net-(JP2-Pad1)") (class "Default")
      (node (ref "JP2") (pin "1") (pinfunction "1_1") (pintype "passive"))
      (node (ref "R3") (pin "1") (pinfunction "1_1") (pintype "passive"))
    )
    (net (code "108") (name "Net-(JP2-Pad2)") (class "Default")
      (node (ref "JP2") (pin "2") (pinfunction "2_2") (pintype "passive"))
      (node (ref "R2") (pin "1") (pinfunction "1_1") (pintype "passive"))
    )
    (net (code "109") (name "Net-(LED1-GRN)") (class "Default")
      (node (ref "LED1") (pin "1") (pinfunction "GRN_1") (pintype "bidirectional"))
      (node (ref "R10") (pin "2") (pinfunction "2_2") (pintype "passive"))
    )
    (net (code "110") (name "Net-(LED1-RED)") (class "Default")
      (node (ref "LED1") (pin "3") (pinfunction "RED_3") (pintype "bidirectional"))
      (node (ref "R9") (pin "2") (pinfunction "2_2") (pintype "passive"))
    )
    (net (code "111") (name "Net-(LED2-GRN)") (class "Default")
      (node (ref "LED2") (pin "1") (pinfunction "GRN_1") (pintype "bidirectional"))
      (node (ref "R12") (pin "2") (pinfunction "2_2") (pintype "passive"))
    )
    (net (code "112") (name "Net-(LED2-RED)") (class "Default")
      (node (ref "LED2") (pin "3") (pinfunction "RED_3") (pintype "bidirectional"))
      (node (ref "R11") (pin "2") (pinfunction "2_2") (pintype "passive"))
    )
    (net (code "113") (name "Net-(LED3-GRN)") (class "Default")
      (node (ref "LED3") (pin "1") (pinfunction "GRN_1") (pintype "bidirectional"))
      (node (ref "R18") (pin "2") (pinfunction "2_2") (pintype "passive"))
    )
    (net (code "114") (name "Net-(LED3-RED)") (class "Default")
      (node (ref "LED3") (pin "3") (pinfunction "RED_3") (pintype "bidirectional"))
      (node (ref "R19") (pin "2") (pinfunction "2_2") (pintype "passive"))
    )
    (net (code "115") (name "Net-(LED4-GRN)") (class "Default")
      (node (ref "LED4") (pin "1") (pinfunction "GRN_1") (pintype "bidirectional"))
      (node (ref "R17") (pin "2") (pinfunction "2_2") (pintype "passive"))
    )
    (net (code "116") (name "Net-(LED4-RED)") (class "Default")
      (node (ref "LED4") (pin "3") (pinfunction "RED_3") (pintype "bidirectional"))
      (node (ref "R15") (pin "2") (pinfunction "2_2") (pintype "passive"))
    )
    (net (code "117") (name "Net-(LED5-GRN)") (class "Default")
      (node (ref "LED5") (pin "1") (pinfunction "GRN_1") (pintype "bidirectional"))
      (node (ref "R36") (pin "2") (pinfunction "2_2") (pintype "passive"))
    )
    (net (code "118") (name "Net-(LED6-Pad2)") (class "Default")
      (node (ref "LED6") (pin "2") (pinfunction "2_2") (pintype "bidirectional"))
      (node (ref "R82") (pin "2") (pinfunction "2_2") (pintype "passive"))
    )
    (net (code "119") (name "Net-(LED7-Pad2)") (class "Default")
      (node (ref "LED7") (pin "2") (pinfunction "2_2") (pintype "bidirectional"))
      (node (ref "R83") (pin "2") (pinfunction "2_2") (pintype "passive"))
    )
    (net (code "120") (name "Net-(LED8-Pad2)") (class "Default")
      (node (ref "LED8") (pin "2") (pinfunction "2_2") (pintype "bidirectional"))
      (node (ref "R84") (pin "2") (pinfunction "2_2") (pintype "passive"))
    )
    (net (code "121") (name "Net-(Q1B-2)") (class "Default")
      (node (ref "C4") (pin "2") (pinfunction "2_2") (pintype "passive"))
      (node (ref "Q1") (pin "3") (pinfunction "2_3") (pintype "passive"))
      (node (ref "R8") (pin "2") (pinfunction "2_2") (pintype "passive"))
    )
    (net (code "122") (name "Net-(R1-Pad2)") (class "Default")
      (node (ref "R1") (pin "2") (pinfunction "2_2") (pintype "passive"))
      (node (ref "SW1") (pin "L1") (pinfunction "L1_L1") (pintype "passive"))
    )
    (net (code "123") (name "Net-(R5-Pad2)") (class "Default")
      (node (ref "R5") (pin "2") (pinfunction "2_2") (pintype "passive"))
      (node (ref "SW2") (pin "L1") (pinfunction "L1_L1") (pintype "passive"))
    )
    (net (code "124") (name "RESET") (class "Default")
      (node (ref "C7") (pin "1") (pinfunction "1_1") (pintype "passive"))
      (node (ref "IC2") (pin "7") (pinfunction "NRST_7") (pintype "bidirectional"))
      (node (ref "JP1") (pin "4") (pinfunction "4_4") (pintype "passive"))
      (node (ref "R6") (pin "1") (pinfunction "1_1") (pintype "passive"))
    )
    (net (code "125") (name "RX") (class "Default")
      (node (ref "IC2") (pin "43") (pinfunction "PA10/USART1_RX/TIM1_CH3_43") (pintype "bidirectional"))
      (node (ref "R3") (pin "2") (pinfunction "2_2") (pintype "passive"))
    )
    (net (code "126") (name "SWCLK") (class "Default")
      (node (ref "IC2") (pin "49") (pinfunction "PA14/JTCK-SWCLK_49") (pintype "bidirectional"))
      (node (ref "JP1") (pin "3") (pinfunction "3_3") (pintype "passive"))
    )
    (net (code "127") (name "SWDIO") (class "Default")
      (node (ref "IC2") (pin "46") (pinfunction "PA13/JTMS-SWDAT_46") (pintype "bidirectional"))
      (node (ref "JP1") (pin "2") (pinfunction "2_2") (pintype "passive"))
    )
    (net (code "128") (name "SW_T_DV") (class "Default")
      (node (ref "IC2") (pin "30") (pinfunction "PB11/I2C2_SDA/USART3_RX_30") (pintype "bidirectional"))
      (node (ref "SW1") (pin "P2") (pinfunction "A2_P2") (pintype "passive"))
      (node (ref "SW1") (pin "P5") (pinfunction "B2_P5") (pintype "passive"))
    )
    (net (code "129") (name "SW_T_MODE") (class "Default")
      (node (ref "IC2") (pin "35") (pinfunction "PB14/SPI2_MISO/USART3_RTS/TIM1_CH2N_35") (pintype "bidirectional"))
      (node (ref "SW3") (pin "3") (pinfunction "3_3") (pintype "passive"))
      (node (ref "SW3") (pin "4") (pinfunction "4_4") (pintype "passive"))
    )
    (net (code "130") (name "SW_T_RANGE") (class "Default")
      (node (ref "IC2") (pin "36") (pinfunction "PB15/SPI2_MOSI/I2S2_SD/TIM1_CH3N_36") (pintype "bidirectional"))
      (node (ref "SW5") (pin "3") (pinfunction "3_3") (pintype "passive"))
      (node (ref "SW5") (pin "4") (pinfunction "4_4") (pintype "passive"))
    )
    (net (code "131") (name "SW_X_DV") (class "Default")
      (node (ref "IC2") (pin "4") (pinfunction "PC15/OSC_OUT_4") (pintype "bidirectional"))
      (node (ref "SW2") (pin "P2") (pinfunction "A2_P2") (pintype "passive"))
      (node (ref "SW2") (pin "P5") (pinfunction "B2_P5") (pintype "passive"))
    )
    (net (code "132") (name "SW_X_EXT") (class "Default")
      (node (ref "IC2") (pin "54") (pinfunction "PD2/TIM3-ETR_54") (pintype "bidirectional"))
      (node (ref "SW7") (pin "3") (pinfunction "3_3") (pintype "passive"))
      (node (ref "SW7") (pin "4") (pinfunction "4_4") (pintype "passive"))
    )
    (net (code "133") (name "SW_X_MODE") (class "Default")
      (node (ref "IC2") (pin "2") (pinfunction "PC13-TAMPER-RTC_2") (pintype "bidirectional"))
      (node (ref "SW4") (pin "3") (pinfunction "3_3") (pintype "passive"))
      (node (ref "SW4") (pin "4") (pinfunction "4_4") (pintype "passive"))
    )
    (net (code "134") (name "SW_X_RANGE") (class "Default")
      (node (ref "IC2") (pin "58") (pinfunction "PB6/I2C1_SCL/TIM4_CH1/USART1_TX_58") (pintype "bidirectional"))
      (node (ref "SW6") (pin "3") (pinfunction "3_3") (pintype "passive"))
      (node (ref "SW6") (pin "4") (pinfunction "4_4") (pintype "passive"))
    )
    (net (code "135") (name "TX") (class "Default")
      (node (ref "IC2") (pin "42") (pinfunction "PA9/USART1_TX/TIM1_CH2_42") (pintype "bidirectional"))
      (node (ref "R2") (pin "2") (pinfunction "2_2") (pintype "passive"))
    )
    (net (code "136") (name "T_CLOCK") (class "Default")
      (node (ref "IC2") (pin "40") (pinfunction "PC9/I2S2_CKIN/I2S3_CKIN_40") (pintype "bidirectional"))
      (node (ref "Q2") (pin "C") (pinfunction "C_C") (pintype "passive"))
      (node (ref "R22") (pin "1") (pinfunction "1_1") (pintype "passive"))
    )
    (net (code "137") (name "VCC") (class "Default")
      (node (ref "C11") (pin "+") (pinfunction "+_+") (pintype "passive"))
      (node (ref "C39") (pin "1") (pinfunction "1_1") (pintype "passive"))
      (node (ref "C48") (pin "1") (pinfunction "1_1") (pintype "passive"))
      (node (ref "C50") (pin "1") (pinfunction "1_1") (pintype "passive"))
      (node (ref "IC10") (pin "4") (pinfunction "V+_4") (pintype "power_in"))
      (node (ref "IC7") (pin "4") (pinfunction "V+_4") (pintype "power_in"))
      (node (ref "IC9") (pin "4") (pinfunction "V+_4") (pintype "power_in"))
      (node (ref "L2") (pin "1") (pinfunction "1_1") (pintype "passive"))
    )
    (net (code "138") (name "VEE") (class "Default")
      (node (ref "C22") (pin "-") (pinfunction "-_-") (pintype "passive"))
      (node (ref "C37") (pin "2") (pinfunction "2_2") (pintype "passive"))
      (node (ref "C49") (pin "2") (pinfunction "2_2") (pintype "passive"))
      (node (ref "IC10") (pin "11") (pinfunction "V-_11") (pintype "power_in"))
      (node (ref "IC7") (pin "11") (pinfunction "V-_11") (pintype "power_in"))
      (node (ref "L4") (pin "1") (pinfunction "1_1") (pintype "passive"))
      (node (ref "R68") (pin "1") (pinfunction "1_1") (pintype "passive"))
    )
    (net (code "139") (name "VREF") (class "Default")
      (node (ref "C25") (pin "1") (pinfunction "1_1") (pintype "passive"))
      (node (ref "IC4") (pin "3") (pinfunction "VREFH_3") (pintype "bidirectional"))
      (node (ref "R74") (pin "2") (pinfunction "2_2") (pintype "passive"))
    )
    (net (code "140") (name "VREF_BIAS") (class "Default")
      (node (ref "C51") (pin "1") (pinfunction "1_1") (pintype "passive"))
      (node (ref "IC7") (pin "10") (pinfunction "+IN_10") (pintype "input"))
      (node (ref "IC7") (pin "12") (pinfunction "+IN_12") (pintype "input"))
      (node (ref "IC7") (pin "3") (pinfunction "+IN_3") (pintype "input"))
      (node (ref "IC7") (pin "5") (pinfunction "+IN_5") (pintype "input"))
      (node (ref "R73") (pin "2") (pinfunction "2_2") (pintype "passive"))
      (node (ref "R74") (pin "1") (pinfunction "1_1") (pintype "passive"))
    )
    (net (code "141") (name "X_CLOCK") (class "Default")
      (node (ref "IC2") (pin "41") (pinfunction "PA8/USART1_CK/TIM1_CH1/MCO_41") (pintype "bidirectional"))
      (node (ref "Q3") (pin "C") (pinfunction "C_C") (pintype "passive"))
      (node (ref "R23") (pin "1") (pinfunction "1_1") (pintype "passive"))
    )
    (net (code "142") (name "unconnected-(IC2-PC14{slash}OSC32_IN-Pad3)") (class "Default")
      (node (ref "IC2") (pin "3") (pinfunction "PC14/OSC32_IN_3") (pintype "bidirectional"))
    )
    (net (code "143") (name "unconnected-(J10-2-PadP2)") (class "Default")
      (node (ref "J10") (pin "P2") (pinfunction "2_P2") (pintype "passive"))
    )
    (net (code "144") (name "unconnected-(J11-2-PadP2)") (class "Default")
      (node (ref "J11") (pin "P2") (pinfunction "2_P2") (pintype "passive"))
    )
    (net (code "145") (name "unconnected-(J12-2-PadP2)") (class "Default")
      (node (ref "J12") (pin "P2") (pinfunction "2_P2") (pintype "passive"))
    )
    (net (code "146") (name "unconnected-(J13-2-PadP2)") (class "Default")
      (node (ref "J13") (pin "P2") (pinfunction "2_P2") (pintype "passive"))
    )
    (net (code "147") (name "unconnected-(J14-2-PadP2)") (class "Default")
      (node (ref "J14") (pin "P2") (pinfunction "2_P2") (pintype "passive"))
    )
    (net (code "148") (name "unconnected-(J15-2-PadP2)") (class "Default")
      (node (ref "J15") (pin "P2") (pinfunction "2_P2") (pintype "passive"))
    )
    (net (code "149") (name "unconnected-(J16-2-PadP2)") (class "Default")
      (node (ref "J16") (pin "P2") (pinfunction "2_P2") (pintype "passive"))
    )
    (net (code "150") (name "unconnected-(LED5-RED-Pad3)") (class "Default")
      (node (ref "LED5") (pin "3") (pinfunction "RED_3") (pintype "bidirectional"))
    )
    (net (code "151") (name "unconnected-(SW1A-A1-PadP1)") (class "Default")
      (node (ref "SW1") (pin "P1") (pinfunction "A1_P1") (pintype "passive"))
    )
    (net (code "152") (name "unconnected-(SW1A-B1-PadP4)") (class "Default")
      (node (ref "SW1") (pin "P4") (pinfunction "B1_P4") (pintype "passive"))
    )
    (net (code "153") (name "unconnected-(SW2A-A1-PadP1)") (class "Default")
      (node (ref "SW2") (pin "P1") (pinfunction "A1_P1") (pintype "passive"))
    )
    (net (code "154") (name "unconnected-(SW2A-B1-PadP4)") (class "Default")
      (node (ref "SW2") (pin "P4") (pinfunction "B1_P4") (pintype "passive"))
    )
  )
)
